# Beilage.net
KiCad netlist of a schematic drawn in EAGLE
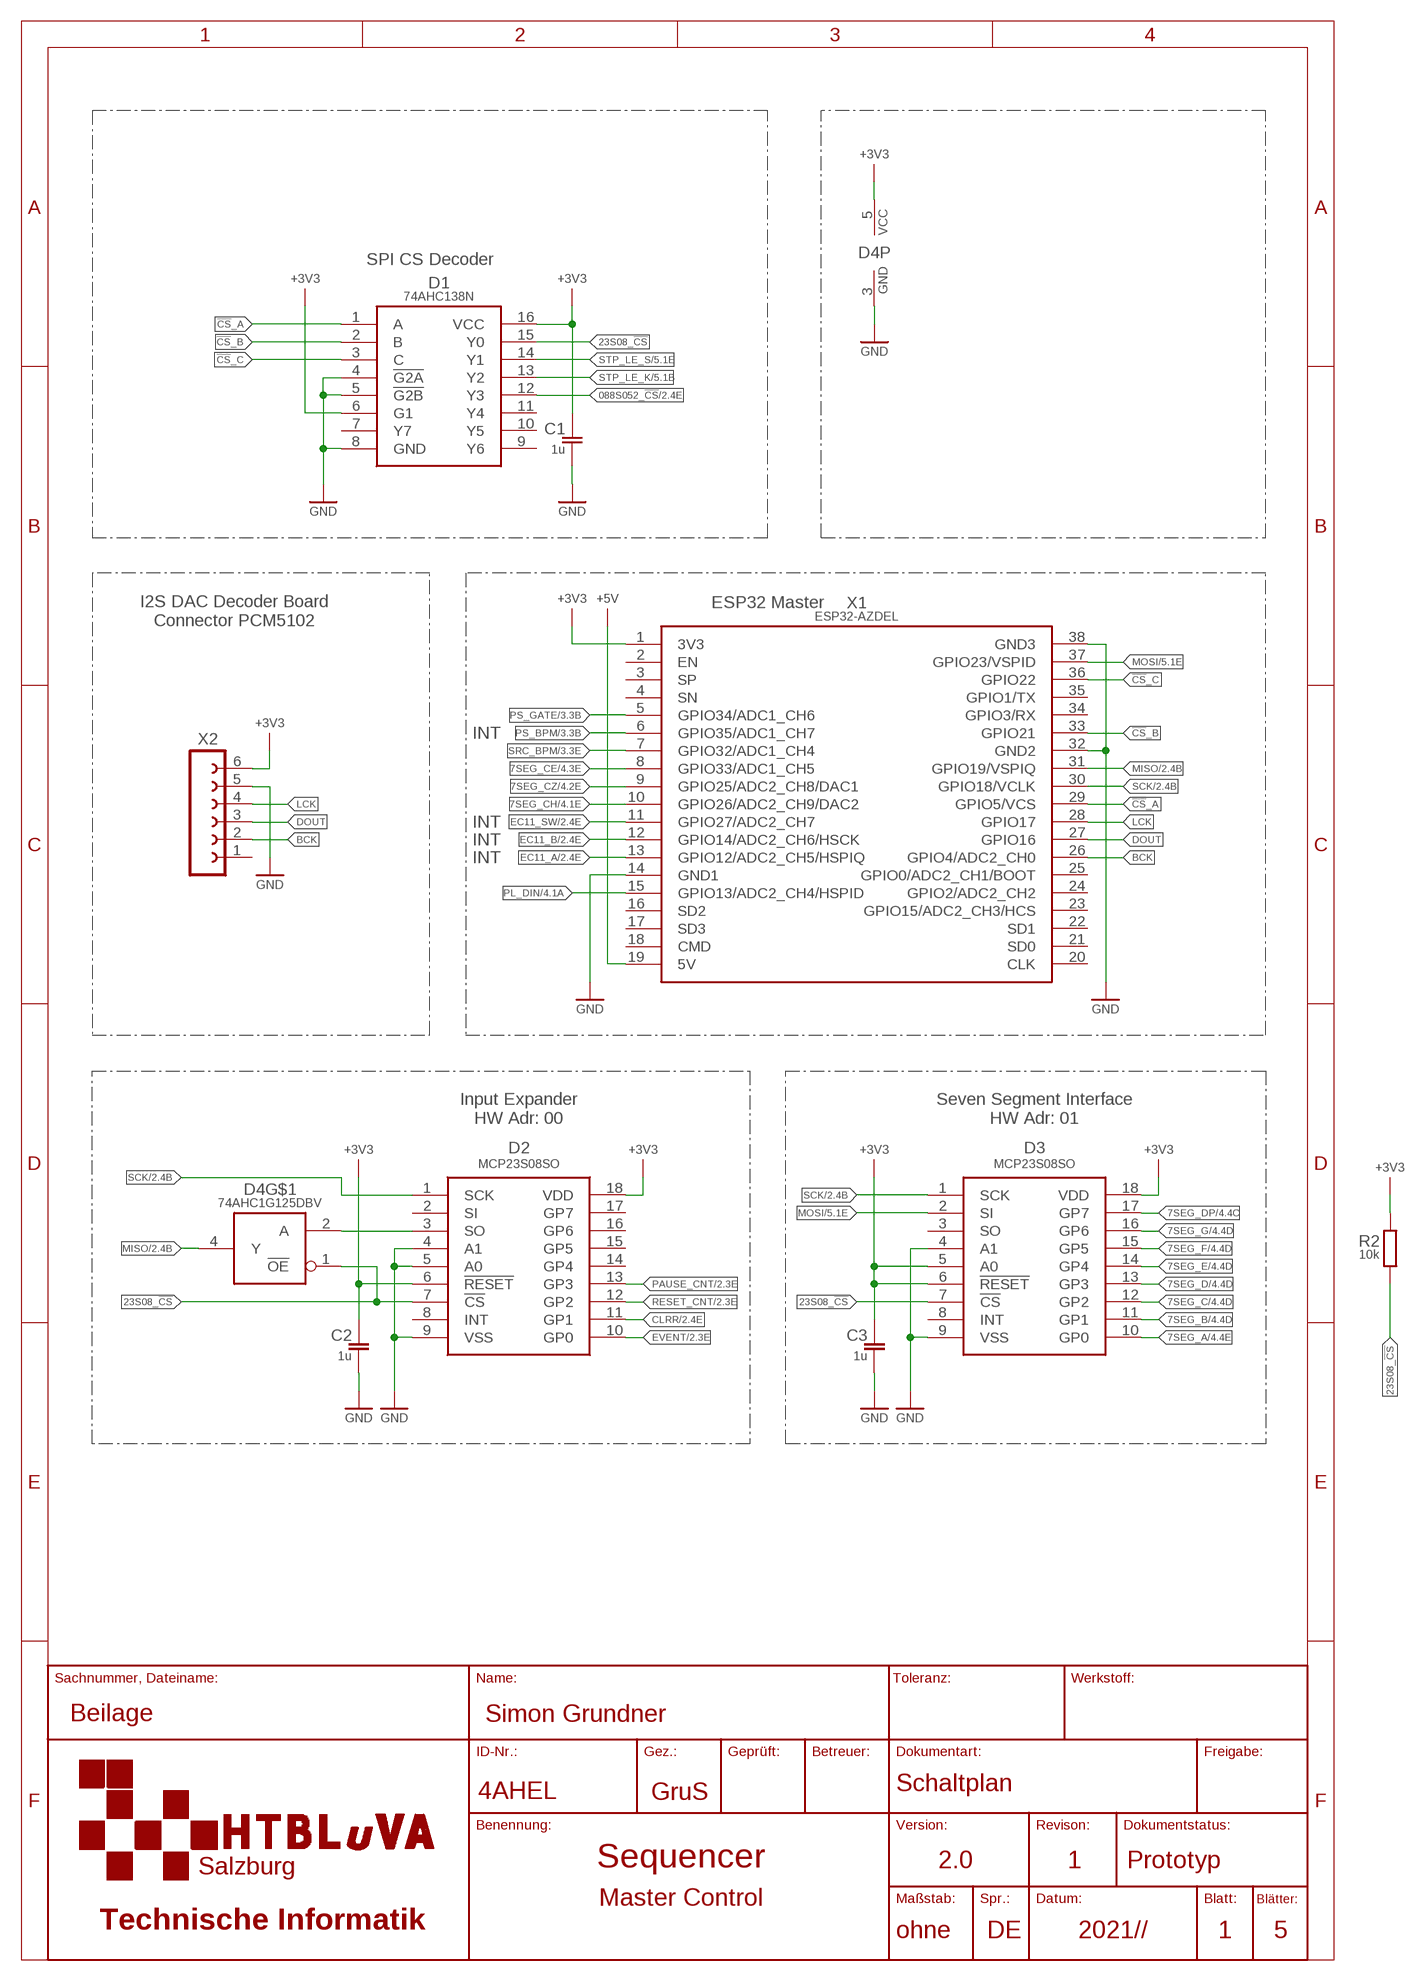
[diagram p0: schematic, sheet 1]
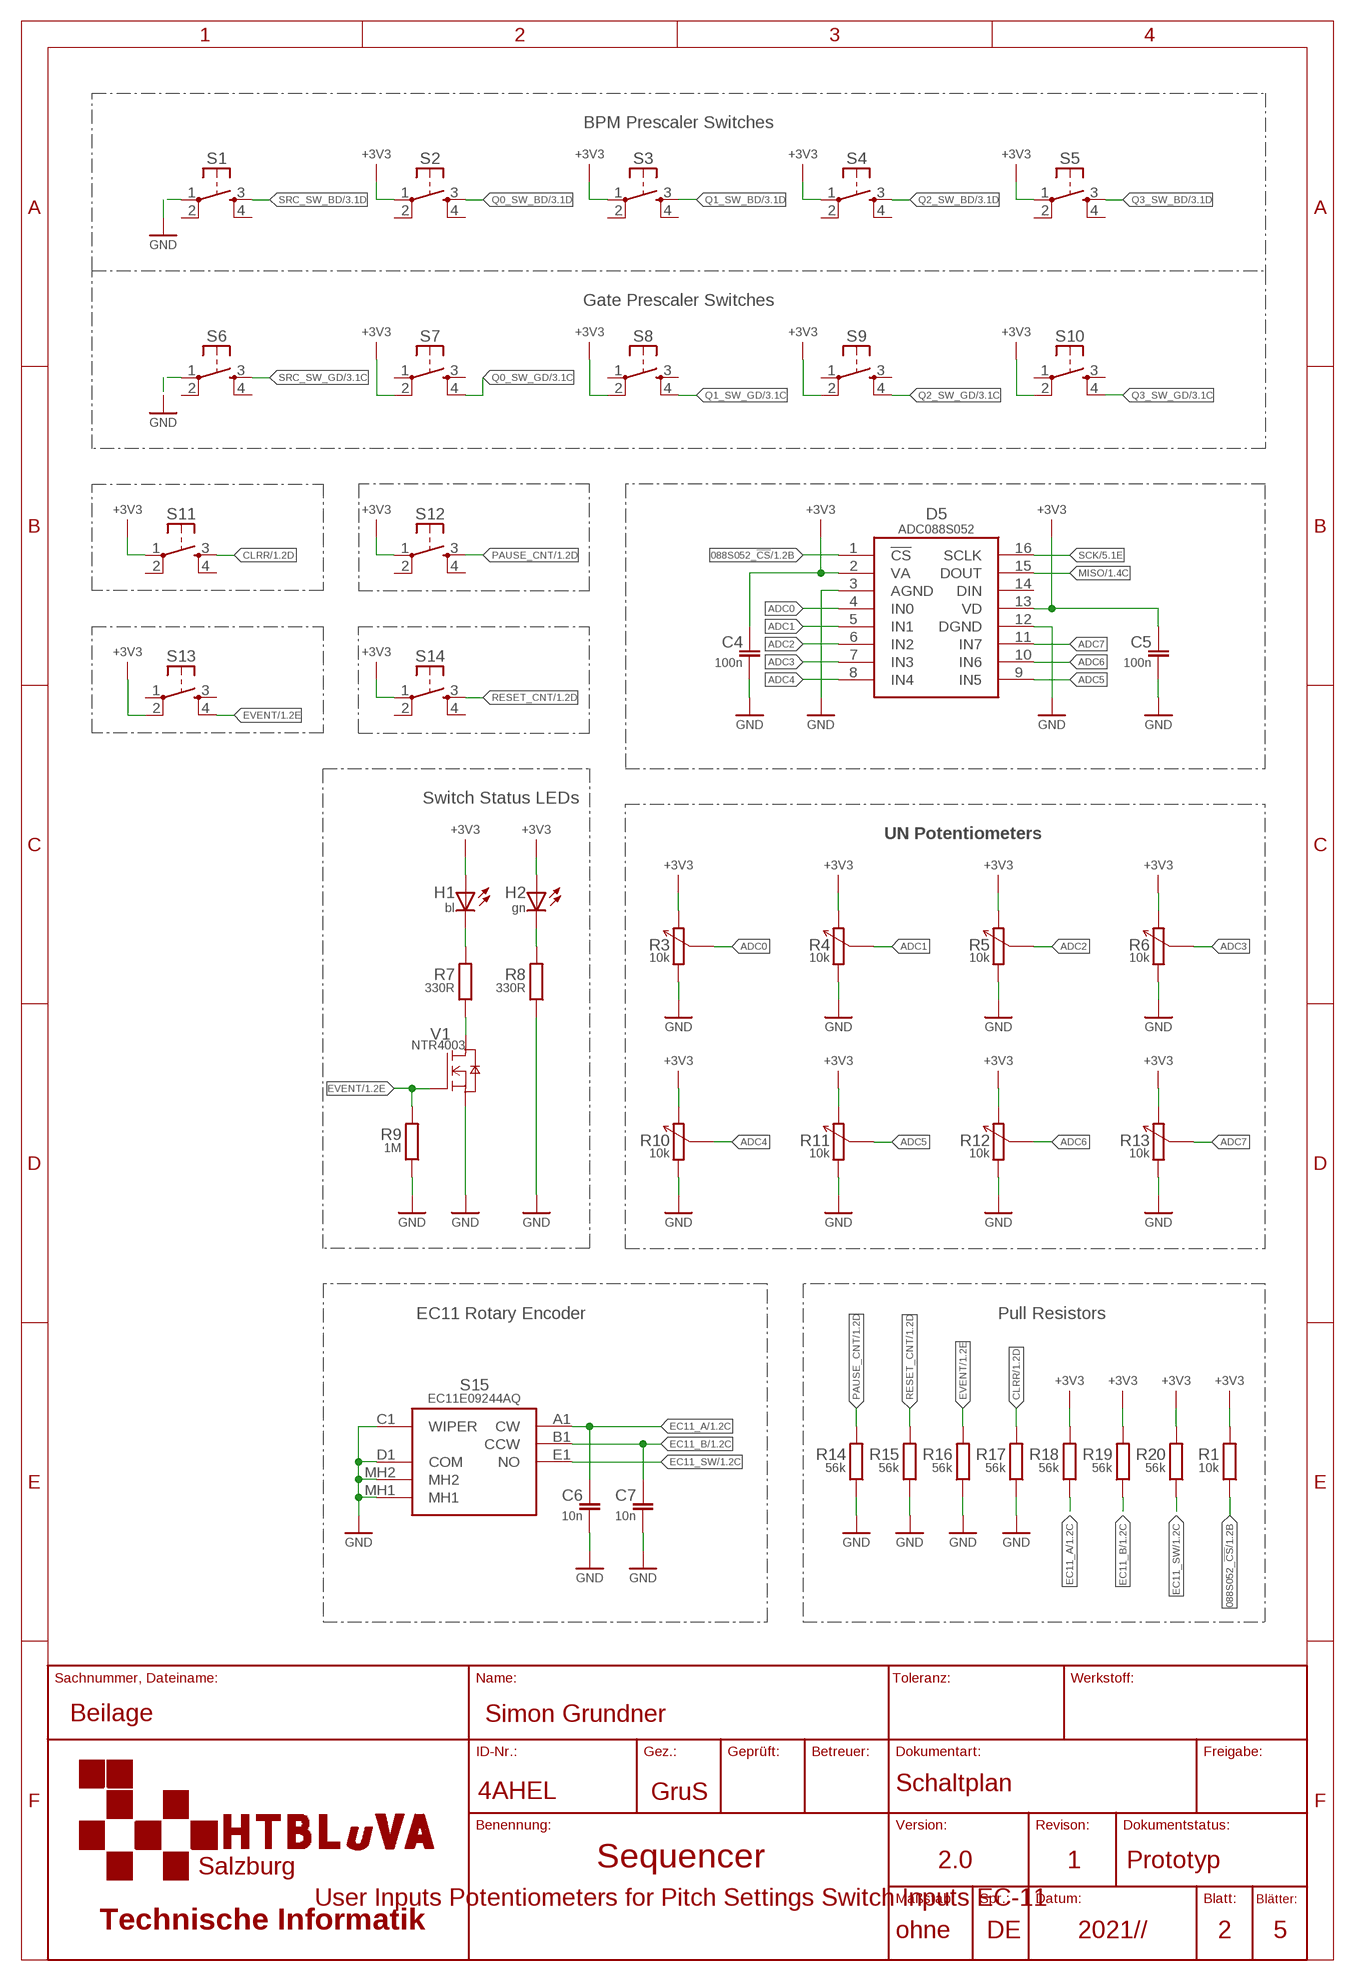
[diagram p1: schematic, sheet 2]
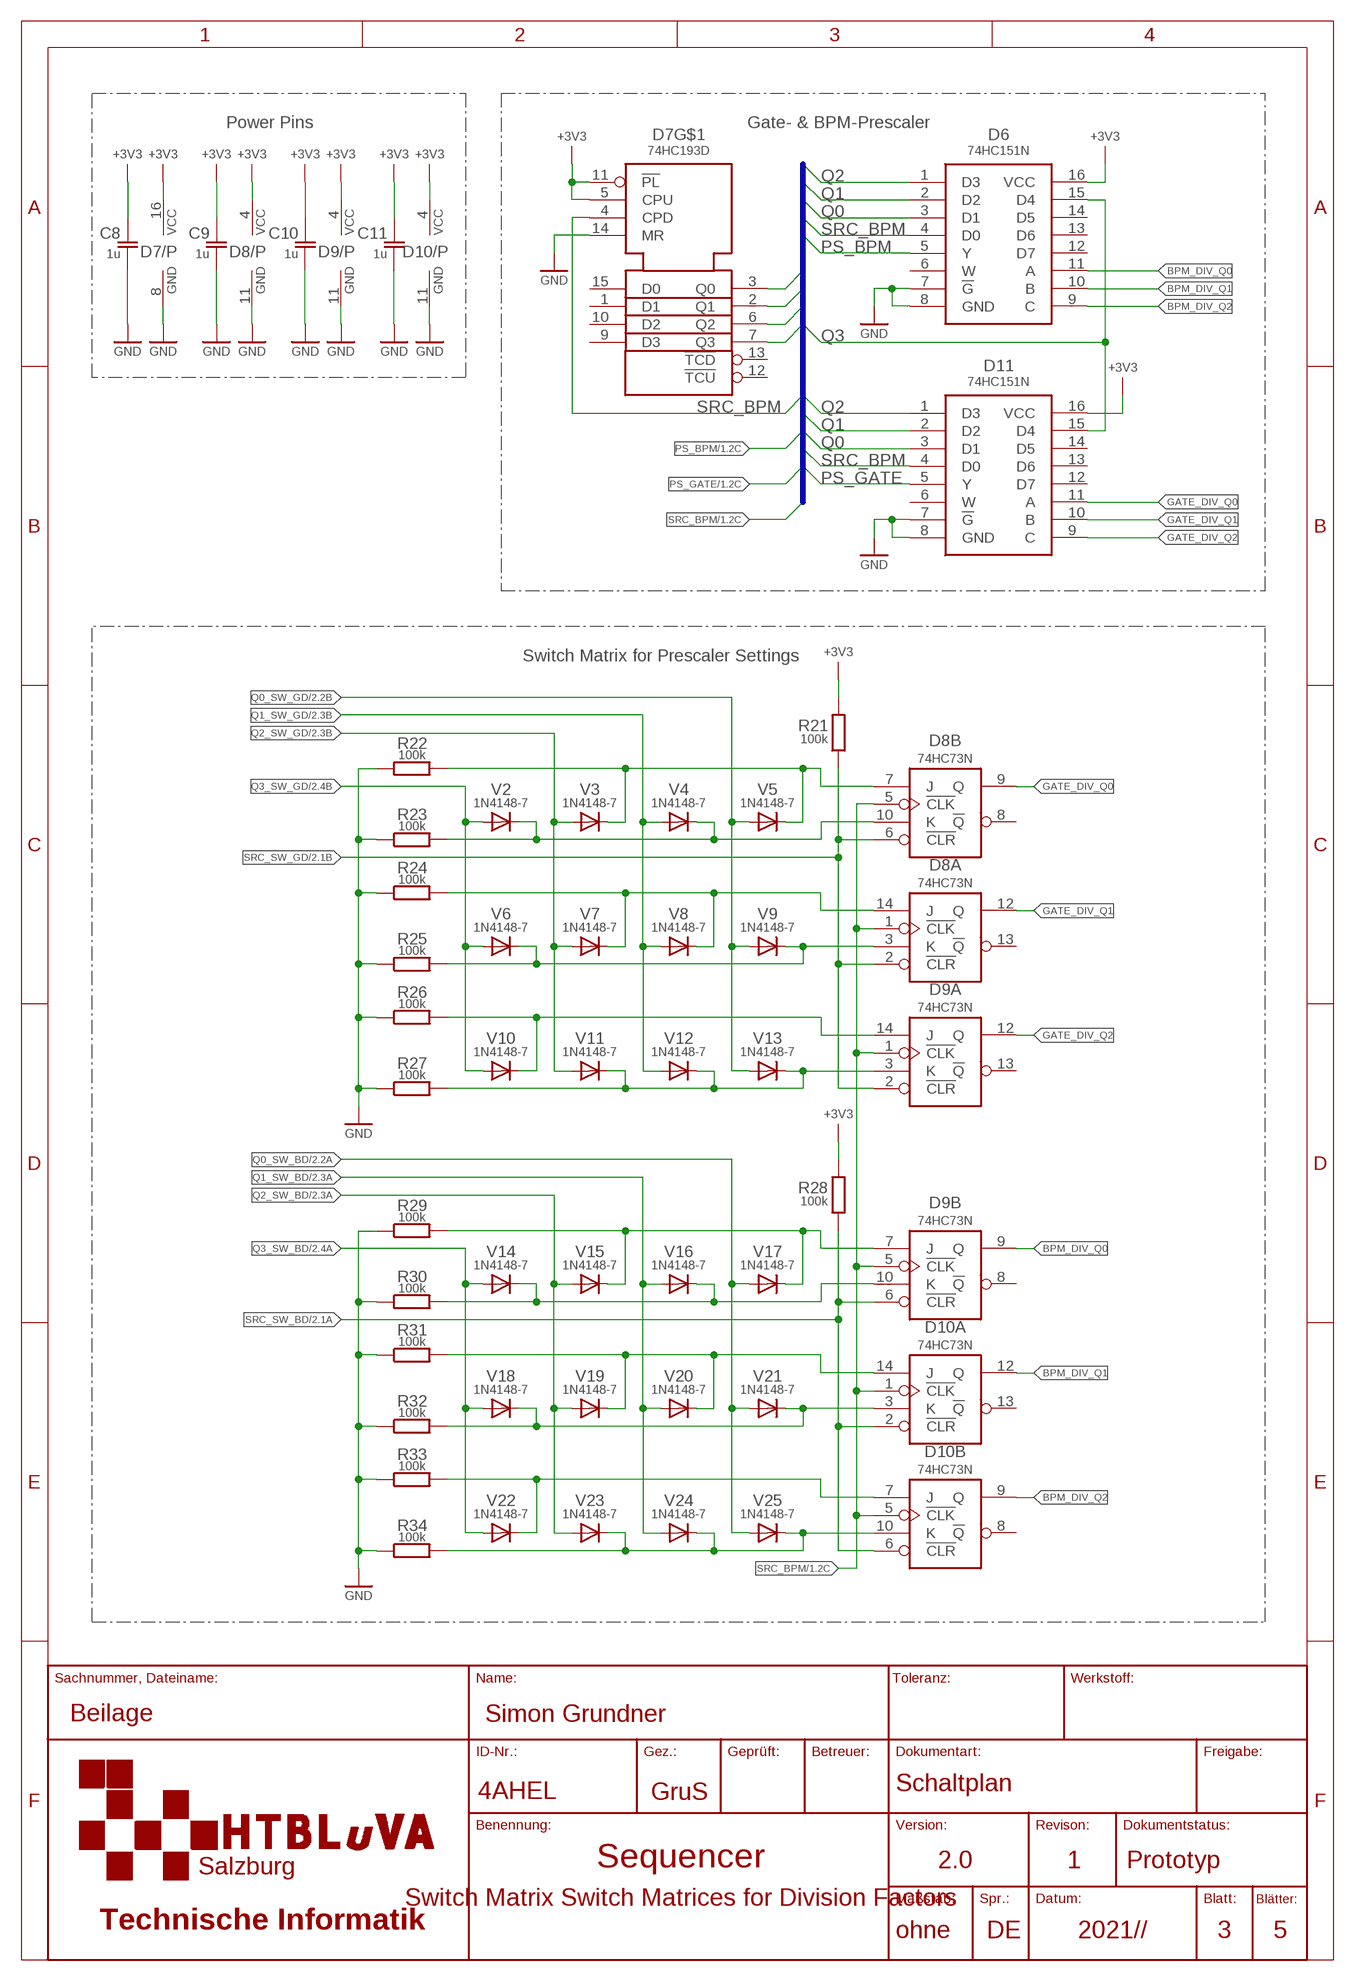
[diagram p2: schematic, sheet 3]
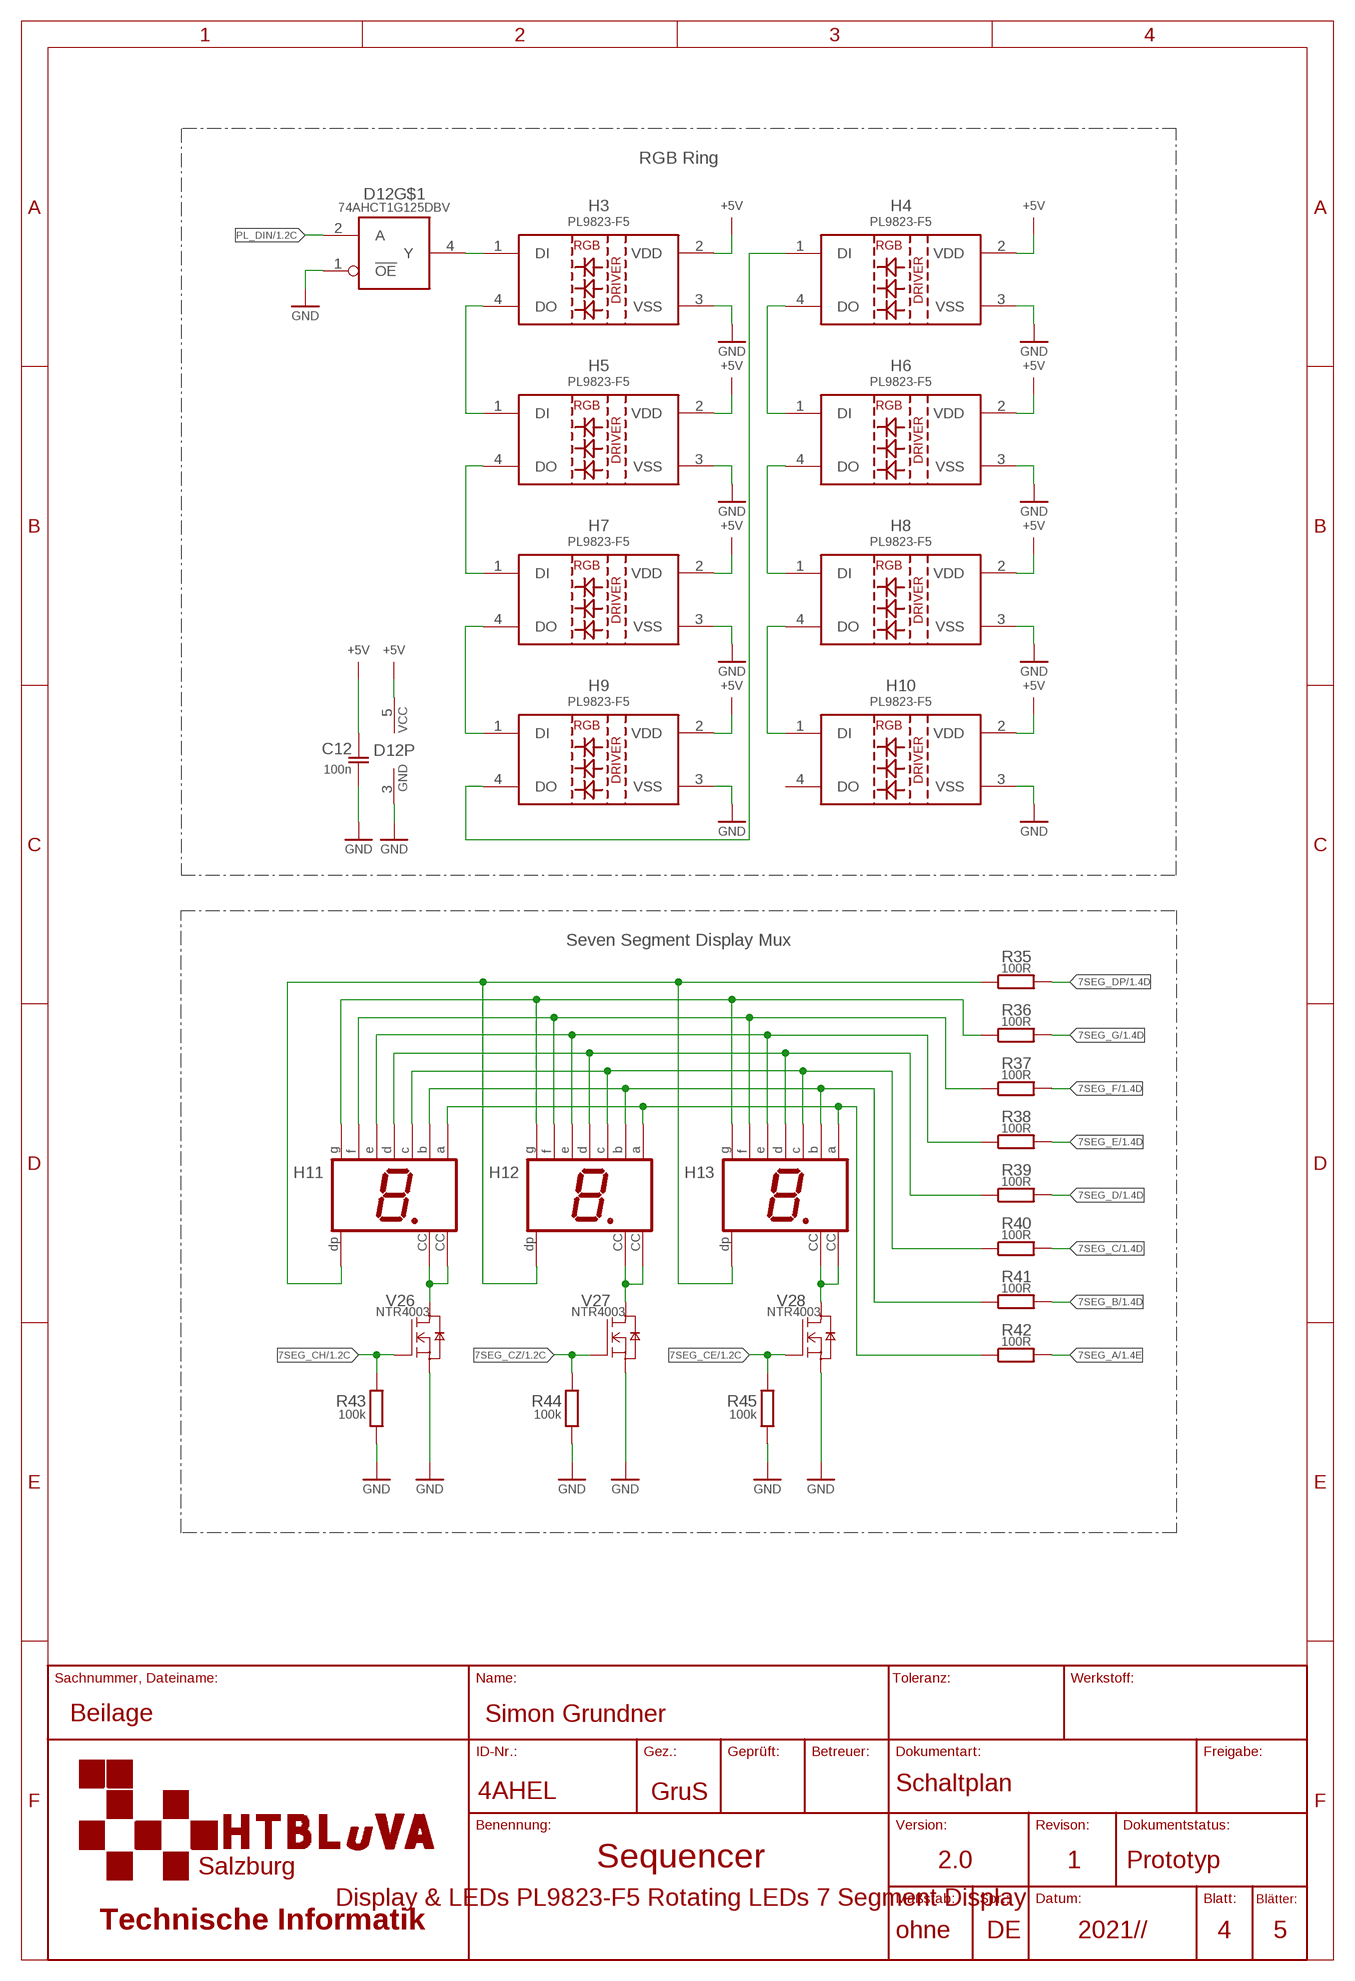
[diagram p3: schematic, sheet 4]
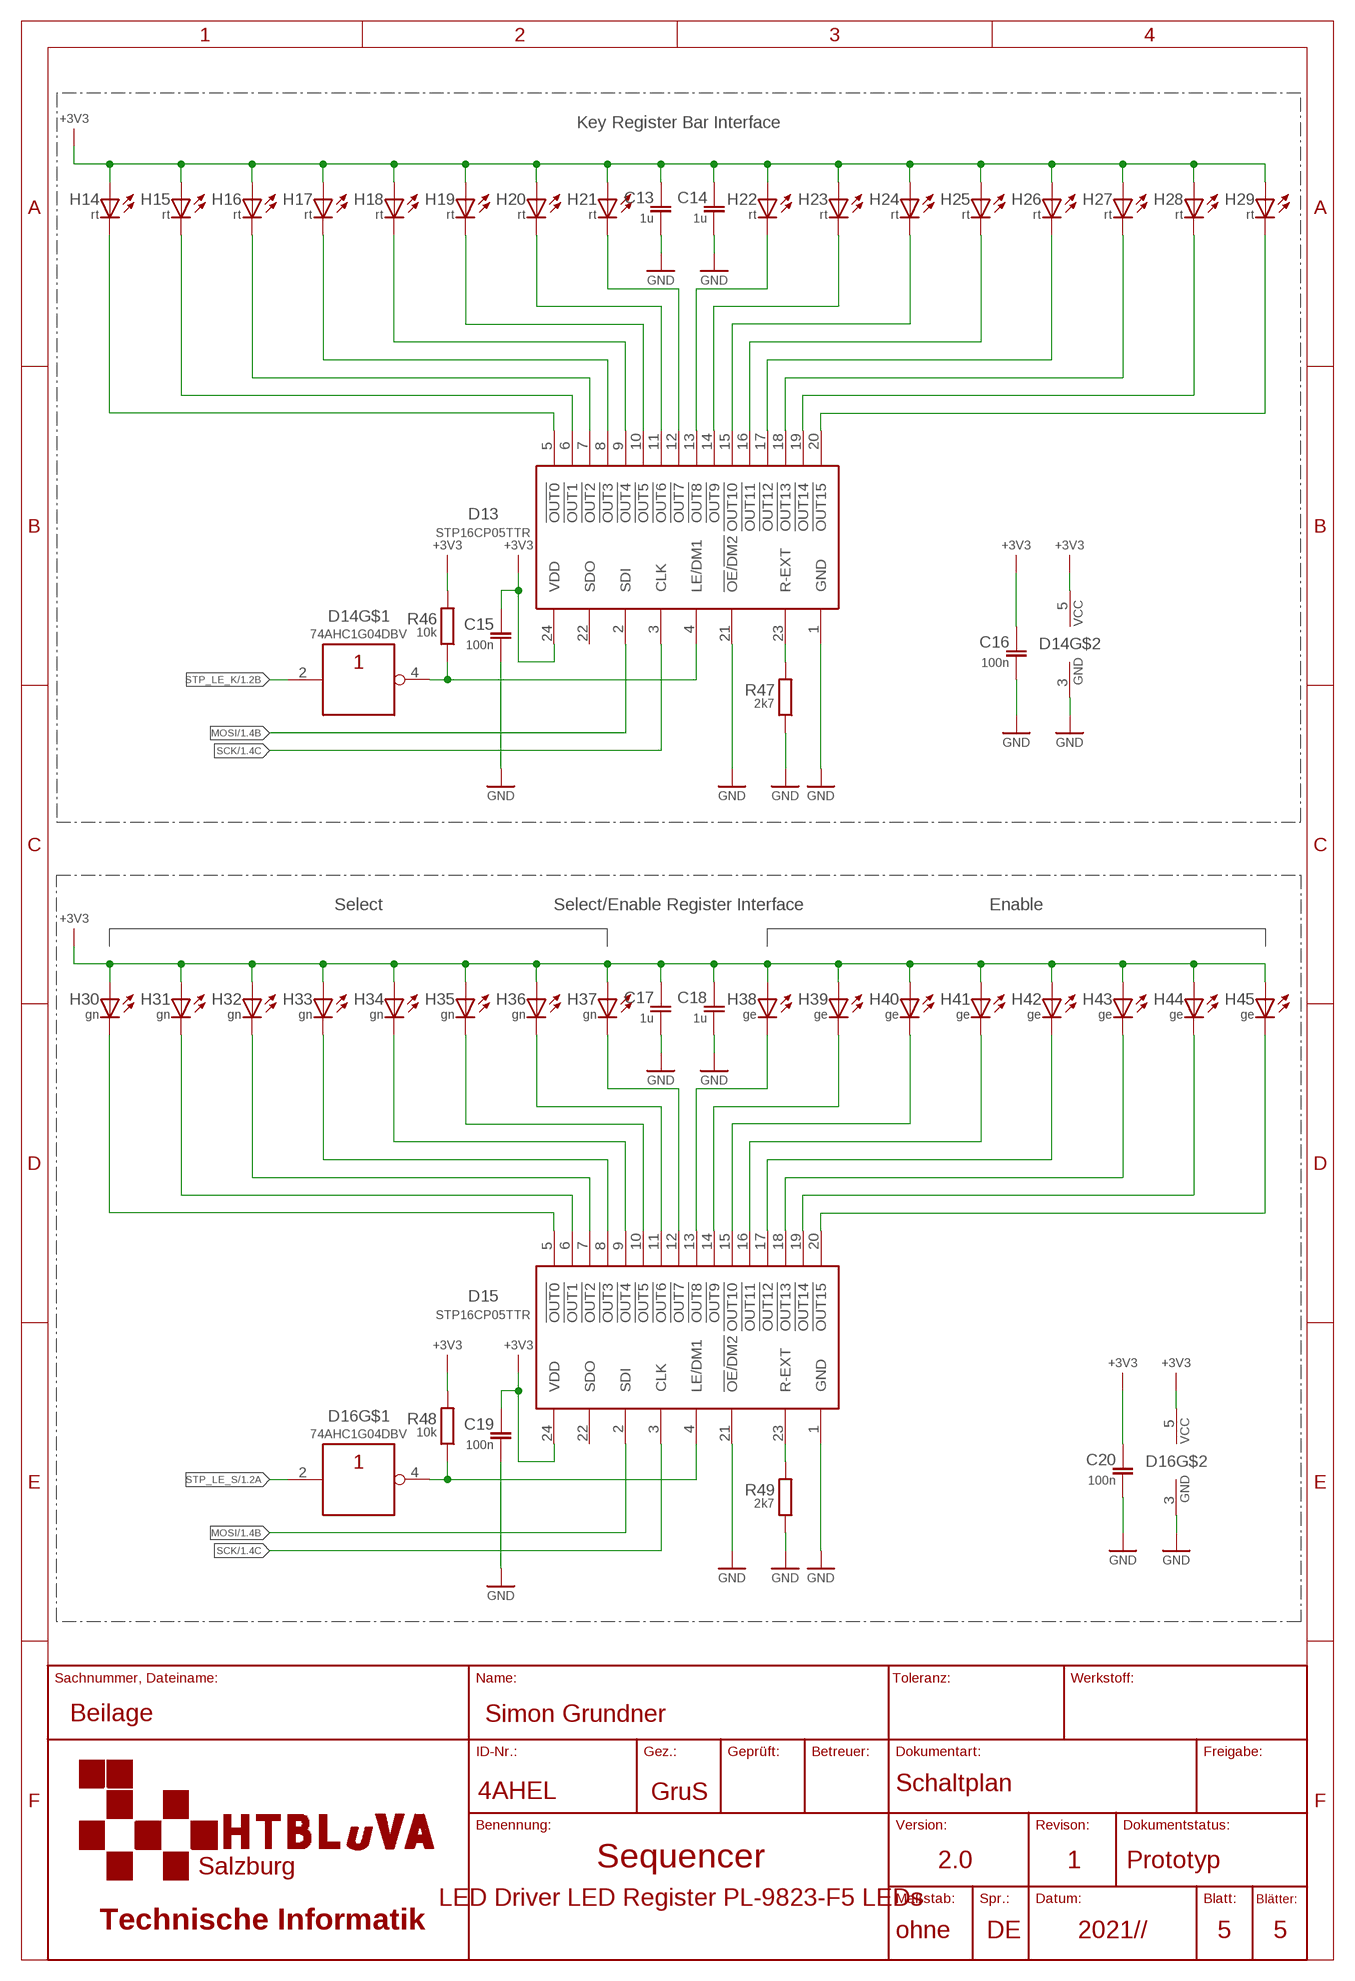
[diagram p4: schematic, sheet 5]

(export (version "E")
  (design (tool "Eeschema 10.0.6"))
  (components
    (comp (ref "C8")
      (value "1u")
      (footprint "eagle-import:C0805")
      (libsource (lib "eagle-import") (part "C-EUC0805"))
    )
    (comp (ref "C9")
      (value "1u")
      (footprint "eagle-import:C0805")
      (libsource (lib "eagle-import") (part "C-EUC0805"))
    )
    (comp (ref "C10")
      (value "1u")
      (footprint "eagle-import:C0805")
      (libsource (lib "eagle-import") (part "C-EUC0805"))
    )
    (comp (ref "C11")
      (value "1u")
      (footprint "eagle-import:C0805")
      (libsource (lib "eagle-import") (part "C-EUC0805"))
    )
    (comp (ref "D6")
      (value "74HC151N")
      (footprint "eagle-import:DIP16")
      (libsource (lib "eagle-import") (part "74151NHC"))
    )
    (comp (ref "D7")
      (value "74HC193D")
      (footprint "eagle-import:SO16")
      (fields (field (name "CATEGORY") "13"))
      (libsource (lib "eagle-import") (part "74193DHC"))
    )
    (comp (ref "D8")
      (value "74HC73N")
      (footprint "eagle-import:DIP14")
      (fields (field (name "CATEGORY") "13"))
      (libsource (lib "eagle-import") (part "7473NHC"))
    )
    (comp (ref "D9")
      (value "74HC73N")
      (footprint "eagle-import:DIP14")
      (fields (field (name "CATEGORY") "13"))
      (libsource (lib "eagle-import") (part "7473NHC"))
    )
    (comp (ref "D10")
      (value "74HC73N")
      (footprint "eagle-import:DIP14")
      (fields (field (name "CATEGORY") "13"))
      (libsource (lib "eagle-import") (part "7473NHC"))
    )
    (comp (ref "D11")
      (value "74HC151N")
      (footprint "eagle-import:DIP16")
      (libsource (lib "eagle-import") (part "74151NHC"))
    )
    (comp (ref "R21")
      (value "100k")
      (footprint "eagle-import:R0805")
      (libsource (lib "eagle-import") (part "R-EUSR0805"))
    )
    (comp (ref "R22")
      (value "100k")
      (footprint "eagle-import:R0805")
      (libsource (lib "eagle-import") (part "R-EU_R0805"))
    )
    (comp (ref "R23")
      (value "100k")
      (footprint "eagle-import:R0805")
      (libsource (lib "eagle-import") (part "R-EU_R0805"))
    )
    (comp (ref "R24")
      (value "100k")
      (footprint "eagle-import:R0805")
      (libsource (lib "eagle-import") (part "R-EU_R0805"))
    )
    (comp (ref "R25")
      (value "100k")
      (footprint "eagle-import:R0805")
      (libsource (lib "eagle-import") (part "R-EU_R0805"))
    )
    (comp (ref "R26")
      (value "100k")
      (footprint "eagle-import:R0805")
      (libsource (lib "eagle-import") (part "R-EU_R0805"))
    )
    (comp (ref "R27")
      (value "100k")
      (footprint "eagle-import:R0805")
      (libsource (lib "eagle-import") (part "R-EU_R0805"))
    )
    (comp (ref "R28")
      (value "100k")
      (footprint "eagle-import:R0805")
      (libsource (lib "eagle-import") (part "R-EUSR0805"))
    )
    (comp (ref "R29")
      (value "100k")
      (footprint "eagle-import:R0805")
      (libsource (lib "eagle-import") (part "R-EU_R0805"))
    )
    (comp (ref "R30")
      (value "100k")
      (footprint "eagle-import:R0805")
      (libsource (lib "eagle-import") (part "R-EU_R0805"))
    )
    (comp (ref "R31")
      (value "100k")
      (footprint "eagle-import:R0805")
      (libsource (lib "eagle-import") (part "R-EU_R0805"))
    )
    (comp (ref "R32")
      (value "100k")
      (footprint "eagle-import:R0805")
      (libsource (lib "eagle-import") (part "R-EU_R0805"))
    )
    (comp (ref "R33")
      (value "100k")
      (footprint "eagle-import:R0805")
      (libsource (lib "eagle-import") (part "R-EU_R0805"))
    )
    (comp (ref "R34")
      (value "100k")
      (footprint "eagle-import:R0805")
      (libsource (lib "eagle-import") (part "R-EU_R0805"))
    )
    (comp (ref "V2")
      (value "1N4148-7")
      (footprint "eagle-import:DO35-7")
      (libsource (lib "eagle-import") (part "1N4148-7"))
    )
    (comp (ref "V3")
      (value "1N4148-7")
      (footprint "eagle-import:DO35-7")
      (libsource (lib "eagle-import") (part "1N4148-7"))
    )
    (comp (ref "V4")
      (value "1N4148-7")
      (footprint "eagle-import:DO35-7")
      (libsource (lib "eagle-import") (part "1N4148-7"))
    )
    (comp (ref "V5")
      (value "1N4148-7")
      (footprint "eagle-import:DO35-7")
      (libsource (lib "eagle-import") (part "1N4148-7"))
    )
    (comp (ref "V6")
      (value "1N4148-7")
      (footprint "eagle-import:DO35-7")
      (libsource (lib "eagle-import") (part "1N4148-7"))
    )
    (comp (ref "V7")
      (value "1N4148-7")
      (footprint "eagle-import:DO35-7")
      (libsource (lib "eagle-import") (part "1N4148-7"))
    )
    (comp (ref "V8")
      (value "1N4148-7")
      (footprint "eagle-import:DO35-7")
      (libsource (lib "eagle-import") (part "1N4148-7"))
    )
    (comp (ref "V9")
      (value "1N4148-7")
      (footprint "eagle-import:DO35-7")
      (libsource (lib "eagle-import") (part "1N4148-7"))
    )
    (comp (ref "V10")
      (value "1N4148-7")
      (footprint "eagle-import:DO35-7")
      (libsource (lib "eagle-import") (part "1N4148-7"))
    )
    (comp (ref "V11")
      (value "1N4148-7")
      (footprint "eagle-import:DO35-7")
      (libsource (lib "eagle-import") (part "1N4148-7"))
    )
    (comp (ref "V12")
      (value "1N4148-7")
      (footprint "eagle-import:DO35-7")
      (libsource (lib "eagle-import") (part "1N4148-7"))
    )
    (comp (ref "V13")
      (value "1N4148-7")
      (footprint "eagle-import:DO35-7")
      (libsource (lib "eagle-import") (part "1N4148-7"))
    )
    (comp (ref "V14")
      (value "1N4148-7")
      (footprint "eagle-import:DO35-7")
      (libsource (lib "eagle-import") (part "1N4148-7"))
    )
    (comp (ref "V15")
      (value "1N4148-7")
      (footprint "eagle-import:DO35-7")
      (libsource (lib "eagle-import") (part "1N4148-7"))
    )
    (comp (ref "V16")
      (value "1N4148-7")
      (footprint "eagle-import:DO35-7")
      (libsource (lib "eagle-import") (part "1N4148-7"))
    )
    (comp (ref "V17")
      (value "1N4148-7")
      (footprint "eagle-import:DO35-7")
      (libsource (lib "eagle-import") (part "1N4148-7"))
    )
    (comp (ref "V18")
      (value "1N4148-7")
      (footprint "eagle-import:DO35-7")
      (libsource (lib "eagle-import") (part "1N4148-7"))
    )
    (comp (ref "V19")
      (value "1N4148-7")
      (footprint "eagle-import:DO35-7")
      (libsource (lib "eagle-import") (part "1N4148-7"))
    )
    (comp (ref "V20")
      (value "1N4148-7")
      (footprint "eagle-import:DO35-7")
      (libsource (lib "eagle-import") (part "1N4148-7"))
    )
    (comp (ref "V21")
      (value "1N4148-7")
      (footprint "eagle-import:DO35-7")
      (libsource (lib "eagle-import") (part "1N4148-7"))
    )
    (comp (ref "V22")
      (value "1N4148-7")
      (footprint "eagle-import:DO35-7")
      (libsource (lib "eagle-import") (part "1N4148-7"))
    )
    (comp (ref "V23")
      (value "1N4148-7")
      (footprint "eagle-import:DO35-7")
      (libsource (lib "eagle-import") (part "1N4148-7"))
    )
    (comp (ref "V24")
      (value "1N4148-7")
      (footprint "eagle-import:DO35-7")
      (libsource (lib "eagle-import") (part "1N4148-7"))
    )
    (comp (ref "V25")
      (value "1N4148-7")
      (footprint "eagle-import:DO35-7")
      (libsource (lib "eagle-import") (part "1N4148-7"))
    )
    (comp (ref "C13")
      (value "1u")
      (footprint "eagle-import:C0805")
      (libsource (lib "eagle-import") (part "C-EUC0805"))
    )
    (comp (ref "C14")
      (value "1u")
      (footprint "eagle-import:C0805")
      (libsource (lib "eagle-import") (part "C-EUC0805"))
    )
    (comp (ref "C15")
      (value "100n")
      (footprint "eagle-import:C0805")
      (libsource (lib "eagle-import") (part "C-EUC0805"))
    )
    (comp (ref "C16")
      (value "100n")
      (footprint "eagle-import:C0805")
      (libsource (lib "eagle-import") (part "C-EUC0805"))
    )
    (comp (ref "C17")
      (value "1u")
      (footprint "eagle-import:C0805")
      (libsource (lib "eagle-import") (part "C-EUC0805"))
    )
    (comp (ref "C18")
      (value "1u")
      (footprint "eagle-import:C0805")
      (libsource (lib "eagle-import") (part "C-EUC0805"))
    )
    (comp (ref "C19")
      (value "100n")
      (footprint "eagle-import:C0805")
      (libsource (lib "eagle-import") (part "C-EUC0805"))
    )
    (comp (ref "C20")
      (value "100n")
      (footprint "eagle-import:C0805")
      (libsource (lib "eagle-import") (part "C-EUC0805"))
    )
    (comp (ref "D13")
      (value "STP16CP05TTR")
      (footprint "eagle-import:TSSOP24")
      (libsource (lib "eagle-import") (part "STP16CP05TTR"))
    )
    (comp (ref "D14")
      (value "74AHC1G04DBV")
      (footprint "eagle-import:SOT23-5")
      (libsource (lib "eagle-import") (part "741G04DBVAHC"))
    )
    (comp (ref "D15")
      (value "STP16CP05TTR")
      (footprint "eagle-import:TSSOP24")
      (libsource (lib "eagle-import") (part "STP16CP05TTR"))
    )
    (comp (ref "D16")
      (value "74AHC1G04DBV")
      (footprint "eagle-import:SOT23-5")
      (libsource (lib "eagle-import") (part "741G04DBVAHC"))
    )
    (comp (ref "H14")
      (value "rt")
      (footprint "eagle-import:CHIPLED_1206")
      (libsource (lib "eagle-import") (part "LEDCHIPLED_1206"))
    )
    (comp (ref "H15")
      (value "rt")
      (footprint "eagle-import:CHIPLED_1206")
      (libsource (lib "eagle-import") (part "LEDCHIPLED_1206"))
    )
    (comp (ref "H16")
      (value "rt")
      (footprint "eagle-import:CHIPLED_1206")
      (libsource (lib "eagle-import") (part "LEDCHIPLED_1206"))
    )
    (comp (ref "H17")
      (value "rt")
      (footprint "eagle-import:CHIPLED_1206")
      (libsource (lib "eagle-import") (part "LEDCHIPLED_1206"))
    )
    (comp (ref "H18")
      (value "rt")
      (footprint "eagle-import:CHIPLED_1206")
      (libsource (lib "eagle-import") (part "LEDCHIPLED_1206"))
    )
    (comp (ref "H19")
      (value "rt")
      (footprint "eagle-import:CHIPLED_1206")
      (libsource (lib "eagle-import") (part "LEDCHIPLED_1206"))
    )
    (comp (ref "H20")
      (value "rt")
      (footprint "eagle-import:CHIPLED_1206")
      (libsource (lib "eagle-import") (part "LEDCHIPLED_1206"))
    )
    (comp (ref "H21")
      (value "rt")
      (footprint "eagle-import:CHIPLED_1206")
      (libsource (lib "eagle-import") (part "LEDCHIPLED_1206"))
    )
    (comp (ref "H22")
      (value "rt")
      (footprint "eagle-import:CHIPLED_1206")
      (libsource (lib "eagle-import") (part "LEDCHIPLED_1206"))
    )
    (comp (ref "H23")
      (value "rt")
      (footprint "eagle-import:CHIPLED_1206")
      (libsource (lib "eagle-import") (part "LEDCHIPLED_1206"))
    )
    (comp (ref "H24")
      (value "rt")
      (footprint "eagle-import:CHIPLED_1206")
      (libsource (lib "eagle-import") (part "LEDCHIPLED_1206"))
    )
    (comp (ref "H25")
      (value "rt")
      (footprint "eagle-import:CHIPLED_1206")
      (libsource (lib "eagle-import") (part "LEDCHIPLED_1206"))
    )
    (comp (ref "H26")
      (value "rt")
      (footprint "eagle-import:CHIPLED_1206")
      (libsource (lib "eagle-import") (part "LEDCHIPLED_1206"))
    )
    (comp (ref "H27")
      (value "rt")
      (footprint "eagle-import:CHIPLED_1206")
      (libsource (lib "eagle-import") (part "LEDCHIPLED_1206"))
    )
    (comp (ref "H28")
      (value "rt")
      (footprint "eagle-import:CHIPLED_1206")
      (libsource (lib "eagle-import") (part "LEDCHIPLED_1206"))
    )
    (comp (ref "H29")
      (value "rt")
      (footprint "eagle-import:CHIPLED_1206")
      (libsource (lib "eagle-import") (part "LEDCHIPLED_1206"))
    )
    (comp (ref "H30")
      (value "gn")
      (footprint "eagle-import:LED5MM")
      (libsource (lib "eagle-import") (part "LED5MM"))
    )
    (comp (ref "H31")
      (value "gn")
      (footprint "eagle-import:LED5MM")
      (libsource (lib "eagle-import") (part "LED5MM"))
    )
    (comp (ref "H32")
      (value "gn")
      (footprint "eagle-import:LED5MM")
      (libsource (lib "eagle-import") (part "LED5MM"))
    )
    (comp (ref "H33")
      (value "gn")
      (footprint "eagle-import:LED5MM")
      (libsource (lib "eagle-import") (part "LED5MM"))
    )
    (comp (ref "H34")
      (value "gn")
      (footprint "eagle-import:LED5MM")
      (libsource (lib "eagle-import") (part "LED5MM"))
    )
    (comp (ref "H35")
      (value "gn")
      (footprint "eagle-import:LED5MM")
      (libsource (lib "eagle-import") (part "LED5MM"))
    )
    (comp (ref "H36")
      (value "gn")
      (footprint "eagle-import:LED5MM")
      (libsource (lib "eagle-import") (part "LED5MM"))
    )
    (comp (ref "H37")
      (value "gn")
      (footprint "eagle-import:LED5MM")
      (libsource (lib "eagle-import") (part "LED5MM"))
    )
    (comp (ref "H38")
      (value "ge")
      (footprint "eagle-import:LED5MM")
      (libsource (lib "eagle-import") (part "LED5MM"))
    )
    (comp (ref "H39")
      (value "ge")
      (footprint "eagle-import:LED5MM")
      (libsource (lib "eagle-import") (part "LED5MM"))
    )
    (comp (ref "H40")
      (value "ge")
      (footprint "eagle-import:LED5MM")
      (libsource (lib "eagle-import") (part "LED5MM"))
    )
    (comp (ref "H41")
      (value "ge")
      (footprint "eagle-import:LED5MM")
      (libsource (lib "eagle-import") (part "LED5MM"))
    )
    (comp (ref "H42")
      (value "ge")
      (footprint "eagle-import:LED5MM")
      (libsource (lib "eagle-import") (part "LED5MM"))
    )
    (comp (ref "H43")
      (value "ge")
      (footprint "eagle-import:LED5MM")
      (libsource (lib "eagle-import") (part "LED5MM"))
    )
    (comp (ref "H44")
      (value "ge")
      (footprint "eagle-import:LED5MM")
      (libsource (lib "eagle-import") (part "LED5MM"))
    )
    (comp (ref "H45")
      (value "ge")
      (footprint "eagle-import:LED5MM")
      (libsource (lib "eagle-import") (part "LED5MM"))
    )
    (comp (ref "R46")
      (value "10k")
      (footprint "eagle-import:R0805")
      (libsource (lib "eagle-import") (part "R-EUSR0805"))
    )
    (comp (ref "R47")
      (value "2k7")
      (footprint "eagle-import:R0805")
      (libsource (lib "eagle-import") (part "R-EUSR0805"))
    )
    (comp (ref "R48")
      (value "10k")
      (footprint "eagle-import:R0805")
      (libsource (lib "eagle-import") (part "R-EUSR0805"))
    )
    (comp (ref "R49")
      (value "2k7")
      (footprint "eagle-import:R0805")
      (libsource (lib "eagle-import") (part "R-EUSR0805"))
    )
    (comp (ref "C1")
      (value "1u")
      (footprint "eagle-import:C0805")
      (libsource (lib "eagle-import") (part "C-EUC0805"))
    )
    (comp (ref "C2")
      (value "1u")
      (footprint "eagle-import:C0805")
      (libsource (lib "eagle-import") (part "C-EUC0805"))
    )
    (comp (ref "C3")
      (value "1u")
      (footprint "eagle-import:C0805")
      (libsource (lib "eagle-import") (part "C-EUC0805"))
    )
    (comp (ref "D1")
      (value "74AHC138N")
      (footprint "eagle-import:DIP16")
      (libsource (lib "eagle-import") (part "74138NAHC"))
    )
    (comp (ref "D2")
      (value "MCP23S08SO")
      (footprint "eagle-import:SO18W")
      (fields
        (field (name "ARROW_PART_NUMBER") "MCP23S08-E/SO")
        (field (name "MOUSER_PART_NUMBER") "579-MCP23S08-E/SO")
      )
      (libsource (lib "eagle-import") (part "MCP23S08SO"))
    )
    (comp (ref "D3")
      (value "MCP23S08SO")
      (footprint "eagle-import:SO18W")
      (fields
        (field (name "ARROW_PART_NUMBER") "MCP23S08-E/SO")
        (field (name "MOUSER_PART_NUMBER") "579-MCP23S08-E/SO")
      )
      (libsource (lib "eagle-import") (part "MCP23S08SO"))
    )
    (comp (ref "D4")
      (value "74AHC1G125DBV")
      (footprint "eagle-import:SOT23-5")
      (libsource (lib "eagle-import") (part "741G125DBVAHC"))
    )
    (comp (ref "R2")
      (value "10k")
      (footprint "eagle-import:R0805")
      (libsource (lib "eagle-import") (part "R-EUSR0805"))
    )
    (comp (ref "X1")
      (value "ESP32-AZDEL")
      (footprint "eagle-import:ESP32-AZDEL")
      (libsource (lib "eagle-import") (part "ESP32-AZDEL"))
    )
    (comp (ref "X2")
      (value "FE06-1")
      (footprint "eagle-import:FE06")
      (libsource (lib "eagle-import") (part "FE06-1"))
    )
    (comp (ref "C12")
      (value "100n")
      (footprint "eagle-import:C0805")
      (libsource (lib "eagle-import") (part "C-EUC0805"))
    )
    (comp (ref "D12")
      (value "74AHCT1G125DBV")
      (footprint "eagle-import:SOT23-5")
      (fields (field (name "CATEGORY") "13"))
      (libsource (lib "eagle-import") (part "741G125DBVAHCT"))
    )
    (comp (ref "H3")
      (value "PL9823-F5")
      (footprint "eagle-import:LED-PL9823-F5")
      (libsource (lib "eagle-import") (part "PL9823-F5"))
    )
    (comp (ref "H4")
      (value "PL9823-F5")
      (footprint "eagle-import:LED-PL9823-F5")
      (libsource (lib "eagle-import") (part "PL9823-F5"))
    )
    (comp (ref "H5")
      (value "PL9823-F5")
      (footprint "eagle-import:LED-PL9823-F5")
      (libsource (lib "eagle-import") (part "PL9823-F5"))
    )
    (comp (ref "H6")
      (value "PL9823-F5")
      (footprint "eagle-import:LED-PL9823-F5")
      (libsource (lib "eagle-import") (part "PL9823-F5"))
    )
    (comp (ref "H7")
      (value "PL9823-F5")
      (footprint "eagle-import:LED-PL9823-F5")
      (libsource (lib "eagle-import") (part "PL9823-F5"))
    )
    (comp (ref "H8")
      (value "PL9823-F5")
      (footprint "eagle-import:LED-PL9823-F5")
      (libsource (lib "eagle-import") (part "PL9823-F5"))
    )
    (comp (ref "H9")
      (value "PL9823-F5")
      (footprint "eagle-import:LED-PL9823-F5")
      (libsource (lib "eagle-import") (part "PL9823-F5"))
    )
    (comp (ref "H10")
      (value "PL9823-F5")
      (footprint "eagle-import:LED-PL9823-F5")
      (libsource (lib "eagle-import") (part "PL9823-F5"))
    )
    (comp (ref "H11")
      (value "HD-H103")
      (footprint "eagle-import:HDSP-E")
      (libsource (lib "eagle-import") (part "HD-H103"))
    )
    (comp (ref "H12")
      (value "HD-H103")
      (footprint "eagle-import:HDSP-E")
      (libsource (lib "eagle-import") (part "HD-H103"))
    )
    (comp (ref "H13")
      (value "HD-H103")
      (footprint "eagle-import:HDSP-E")
      (libsource (lib "eagle-import") (part "HD-H103"))
    )
    (comp (ref "R35")
      (value "100R")
      (footprint "eagle-import:R0805")
      (libsource (lib "eagle-import") (part "R-EU_R0805"))
    )
    (comp (ref "R36")
      (value "100R")
      (footprint "eagle-import:R0805")
      (libsource (lib "eagle-import") (part "R-EU_R0805"))
    )
    (comp (ref "R37")
      (value "100R")
      (footprint "eagle-import:R0805")
      (libsource (lib "eagle-import") (part "R-EU_R0805"))
    )
    (comp (ref "R38")
      (value "100R")
      (footprint "eagle-import:R0805")
      (libsource (lib "eagle-import") (part "R-EU_R0805"))
    )
    (comp (ref "R39")
      (value "100R")
      (footprint "eagle-import:R0805")
      (libsource (lib "eagle-import") (part "R-EU_R0805"))
    )
    (comp (ref "R40")
      (value "100R")
      (footprint "eagle-import:R0805")
      (libsource (lib "eagle-import") (part "R-EU_R0805"))
    )
    (comp (ref "R41")
      (value "100R")
      (footprint "eagle-import:R0805")
      (libsource (lib "eagle-import") (part "R-EU_R0805"))
    )
    (comp (ref "R42")
      (value "100R")
      (footprint "eagle-import:R0805")
      (libsource (lib "eagle-import") (part "R-EU_R0805"))
    )
    (comp (ref "R43")
      (value "100k")
      (footprint "eagle-import:R0805")
      (libsource (lib "eagle-import") (part "R-EUSR0805"))
    )
    (comp (ref "R44")
      (value "100k")
      (footprint "eagle-import:R0805")
      (libsource (lib "eagle-import") (part "R-EUSR0805"))
    )
    (comp (ref "R45")
      (value "100k")
      (footprint "eagle-import:R0805")
      (libsource (lib "eagle-import") (part "R-EUSR0805"))
    )
    (comp (ref "V26")
      (value "NTR4003")
      (footprint "eagle-import:SOT23")
      (libsource (lib "eagle-import") (part "NTR4003"))
    )
    (comp (ref "V27")
      (value "NTR4003")
      (footprint "eagle-import:SOT23")
      (libsource (lib "eagle-import") (part "NTR4003"))
    )
    (comp (ref "V28")
      (value "NTR4003")
      (footprint "eagle-import:SOT23")
      (libsource (lib "eagle-import") (part "NTR4003"))
    )
    (comp (ref "C4")
      (value "100n")
      (footprint "eagle-import:C0805")
      (libsource (lib "eagle-import") (part "C-EUC0805"))
    )
    (comp (ref "C5")
      (value "100n")
      (footprint "eagle-import:C0805")
      (libsource (lib "eagle-import") (part "C-EUC0805"))
    )
    (comp (ref "C6")
      (value "10n")
      (footprint "eagle-import:C0805")
      (libsource (lib "eagle-import") (part "C-EUC0805"))
    )
    (comp (ref "C7")
      (value "10n")
      (footprint "eagle-import:C0805")
      (libsource (lib "eagle-import") (part "C-EUC0805"))
    )
    (comp (ref "D5")
      (value "ADC088S052")
      (footprint "eagle-import:TSSOP16")
      (fields
        (field (name "ARROW_PART_NUMBER") "ADC088S052CIMT/NOPB")
        (field (name "MOUSER_PART_NUMBER") "926-AD088S052CIMTNPB")
      )
      (libsource (lib "eagle-import") (part "ADC088S052"))
    )
    (comp (ref "H1")
      (value "bl")
      (footprint "eagle-import:CHIPLED_1206")
      (libsource (lib "eagle-import") (part "LEDCHIPLED_1206"))
    )
    (comp (ref "H2")
      (value "gn")
      (footprint "eagle-import:CHIPLED_1206")
      (libsource (lib "eagle-import") (part "LEDCHIPLED_1206"))
    )
    (comp (ref "R1")
      (value "10k")
      (footprint "eagle-import:R0805")
      (libsource (lib "eagle-import") (part "R-EUSR0805"))
    )
    (comp (ref "R3")
      (value "10k")
      (footprint "eagle-import:P160L")
      (libsource (lib "eagle-import") (part "P160L"))
    )
    (comp (ref "R4")
      (value "10k")
      (footprint "eagle-import:P160L")
      (libsource (lib "eagle-import") (part "P160L"))
    )
    (comp (ref "R5")
      (value "10k")
      (footprint "eagle-import:P160L")
      (libsource (lib "eagle-import") (part "P160L"))
    )
    (comp (ref "R6")
      (value "10k")
      (footprint "eagle-import:P160L")
      (libsource (lib "eagle-import") (part "P160L"))
    )
    (comp (ref "R7")
      (value "330R")
      (footprint "eagle-import:R0805")
      (libsource (lib "eagle-import") (part "R-EUSR0805"))
    )
    (comp (ref "R8")
      (value "330R")
      (footprint "eagle-import:R0805")
      (libsource (lib "eagle-import") (part "R-EUSR0805"))
    )
    (comp (ref "R9")
      (value "1M")
      (footprint "eagle-import:R0805")
      (libsource (lib "eagle-import") (part "R-EUSR0805"))
    )
    (comp (ref "R10")
      (value "10k")
      (footprint "eagle-import:P160L")
      (libsource (lib "eagle-import") (part "P160L"))
    )
    (comp (ref "R11")
      (value "10k")
      (footprint "eagle-import:P160L")
      (libsource (lib "eagle-import") (part "P160L"))
    )
    (comp (ref "R12")
      (value "10k")
      (footprint "eagle-import:P160L")
      (libsource (lib "eagle-import") (part "P160L"))
    )
    (comp (ref "R13")
      (value "10k")
      (footprint "eagle-import:P160L")
      (libsource (lib "eagle-import") (part "P160L"))
    )
    (comp (ref "R14")
      (value "56k")
      (footprint "eagle-import:R0805")
      (libsource (lib "eagle-import") (part "R-EUSR0805"))
    )
    (comp (ref "R15")
      (value "56k")
      (footprint "eagle-import:R0805")
      (libsource (lib "eagle-import") (part "R-EUSR0805"))
    )
    (comp (ref "R16")
      (value "56k")
      (footprint "eagle-import:R0805")
      (libsource (lib "eagle-import") (part "R-EUSR0805"))
    )
    (comp (ref "R17")
      (value "56k")
      (footprint "eagle-import:R0805")
      (libsource (lib "eagle-import") (part "R-EUSR0805"))
    )
    (comp (ref "R18")
      (value "56k")
      (footprint "eagle-import:R0805")
      (libsource (lib "eagle-import") (part "R-EUSR0805"))
    )
    (comp (ref "R19")
      (value "56k")
      (footprint "eagle-import:R0805")
      (libsource (lib "eagle-import") (part "R-EUSR0805"))
    )
    (comp (ref "R20")
      (value "56k")
      (footprint "eagle-import:R0805")
      (libsource (lib "eagle-import") (part "R-EUSR0805"))
    )
    (comp (ref "S1")
      (value "TASTE10XX")
      (footprint "eagle-import:B3F-10XX")
      (libsource (lib "eagle-import") (part "TASTE10XX"))
    )
    (comp (ref "S2")
      (value "TASTE10XX")
      (footprint "eagle-import:B3F-10XX")
      (libsource (lib "eagle-import") (part "TASTE10XX"))
    )
    (comp (ref "S3")
      (value "TASTE10XX")
      (footprint "eagle-import:B3F-10XX")
      (libsource (lib "eagle-import") (part "TASTE10XX"))
    )
    (comp (ref "S4")
      (value "TASTE10XX")
      (footprint "eagle-import:B3F-10XX")
      (libsource (lib "eagle-import") (part "TASTE10XX"))
    )
    (comp (ref "S5")
      (value "TASTE10XX")
      (footprint "eagle-import:B3F-10XX")
      (libsource (lib "eagle-import") (part "TASTE10XX"))
    )
    (comp (ref "S6")
      (value "TASTE10XX")
      (footprint "eagle-import:B3F-10XX")
      (libsource (lib "eagle-import") (part "TASTE10XX"))
    )
    (comp (ref "S7")
      (value "TASTE10XX")
      (footprint "eagle-import:B3F-10XX")
      (libsource (lib "eagle-import") (part "TASTE10XX"))
    )
    (comp (ref "S8")
      (value "TASTE10XX")
      (footprint "eagle-import:B3F-10XX")
      (libsource (lib "eagle-import") (part "TASTE10XX"))
    )
    (comp (ref "S9")
      (value "TASTE10XX")
      (footprint "eagle-import:B3F-10XX")
      (libsource (lib "eagle-import") (part "TASTE10XX"))
    )
    (comp (ref "S10")
      (value "TASTE10XX")
      (footprint "eagle-import:B3F-10XX")
      (libsource (lib "eagle-import") (part "TASTE10XX"))
    )
    (comp (ref "S11")
      (value "TASTE10XX")
      (footprint "eagle-import:B3F-10XX")
      (libsource (lib "eagle-import") (part "TASTE10XX"))
    )
    (comp (ref "S12")
      (value "TASTE10XX")
      (footprint "eagle-import:B3F-10XX")
      (libsource (lib "eagle-import") (part "TASTE10XX"))
    )
    (comp (ref "S13")
      (value "TASTE10XX")
      (footprint "eagle-import:B3F-10XX")
      (libsource (lib "eagle-import") (part "TASTE10XX"))
    )
    (comp (ref "S14")
      (value "TASTE10XX")
      (footprint "eagle-import:B3F-10XX")
      (libsource (lib "eagle-import") (part "TASTE10XX"))
    )
    (comp (ref "S15")
      (value "EC11E09244AQ")
      (footprint "eagle-import:EC11")
      (fields (field (name "MOUSER_PART_NUMBER") "688-EC11E09244AQ"))
      (libsource (lib "eagle-import") (part "EC11E09244AQ"))
    )
    (comp (ref "V1")
      (value "NTR4003")
      (footprint "eagle-import:SOT23")
      (libsource (lib "eagle-import") (part "NTR4003"))
    )
  )
  (nets
    (net (code "1") (name "+3V3") (class "Default")
      (node (ref "C1") (pin "1") (pinfunction "1_1") (pintype "passive"))
      (node (ref "C10") (pin "1") (pinfunction "1_1") (pintype "passive"))
      (node (ref "C11") (pin "1") (pinfunction "1_1") (pintype "passive"))
      (node (ref "C13") (pin "1") (pinfunction "1_1") (pintype "passive"))
      (node (ref "C14") (pin "1") (pinfunction "1_1") (pintype "passive"))
      (node (ref "C15") (pin "1") (pinfunction "1_1") (pintype "passive"))
      (node (ref "C16") (pin "1") (pinfunction "1_1") (pintype "passive"))
      (node (ref "C17") (pin "1") (pinfunction "1_1") (pintype "passive"))
      (node (ref "C18") (pin "1") (pinfunction "1_1") (pintype "passive"))
      (node (ref "C19") (pin "1") (pinfunction "1_1") (pintype "passive"))
      (node (ref "C2") (pin "1") (pinfunction "1_1") (pintype "passive"))
      (node (ref "C20") (pin "1") (pinfunction "1_1") (pintype "passive"))
      (node (ref "C3") (pin "1") (pinfunction "1_1") (pintype "passive"))
      (node (ref "C4") (pin "1") (pinfunction "1_1") (pintype "passive"))
      (node (ref "C5") (pin "1") (pinfunction "1_1") (pintype "passive"))
      (node (ref "C8") (pin "1") (pinfunction "1_1") (pintype "passive"))
      (node (ref "C9") (pin "1") (pinfunction "1_1") (pintype "passive"))
      (node (ref "D1") (pin "16") (pinfunction "VCC_16") (pintype "bidirectional"))
      (node (ref "D1") (pin "6") (pinfunction "G1_6") (pintype "bidirectional"))
      (node (ref "D10") (pin "4") (pinfunction "VCC_4") (pintype "power_in"))
      (node (ref "D11") (pin "16") (pinfunction "VCC_16") (pintype "bidirectional"))
      (node (ref "D13") (pin "24") (pinfunction "VDD_24") (pintype "bidirectional"))
      (node (ref "D14") (pin "5") (pinfunction "VCC_5") (pintype "power_in"))
      (node (ref "D15") (pin "24") (pinfunction "VDD_24") (pintype "bidirectional"))
      (node (ref "D16") (pin "5") (pinfunction "VCC_5") (pintype "power_in"))
      (node (ref "D2") (pin "18") (pinfunction "VDD_18") (pintype "bidirectional"))
      (node (ref "D2") (pin "6") (pinfunction "~{RESET}_6") (pintype "bidirectional"))
      (node (ref "D3") (pin "18") (pinfunction "VDD_18") (pintype "bidirectional"))
      (node (ref "D3") (pin "5") (pinfunction "A0_5") (pintype "bidirectional"))
      (node (ref "D3") (pin "6") (pinfunction "~{RESET}_6") (pintype "bidirectional"))
      (node (ref "D4") (pin "5") (pinfunction "VCC_5") (pintype "power_in"))
      (node (ref "D5") (pin "13") (pinfunction "VD_13") (pintype "bidirectional"))
      (node (ref "D5") (pin "2") (pinfunction "VA_2") (pintype "bidirectional"))
      (node (ref "D6") (pin "16") (pinfunction "VCC_16") (pintype "bidirectional"))
      (node (ref "D7") (pin "11") (pinfunction "~{PL}_11") (pintype "input"))
      (node (ref "D7") (pin "16") (pinfunction "VCC_16") (pintype "power_in"))
      (node (ref "D7") (pin "5") (pinfunction "CPU_5") (pintype "input"))
      (node (ref "D8") (pin "4") (pinfunction "VCC_4") (pintype "power_in"))
      (node (ref "D9") (pin "4") (pinfunction "VCC_4") (pintype "power_in"))
      (node (ref "H1") (pin "A") (pinfunction "A_A") (pintype "passive"))
      (node (ref "H14") (pin "A") (pinfunction "A_A") (pintype "passive"))
      (node (ref "H15") (pin "A") (pinfunction "A_A") (pintype "passive"))
      (node (ref "H16") (pin "A") (pinfunction "A_A") (pintype "passive"))
      (node (ref "H17") (pin "A") (pinfunction "A_A") (pintype "passive"))
      (node (ref "H18") (pin "A") (pinfunction "A_A") (pintype "passive"))
      (node (ref "H19") (pin "A") (pinfunction "A_A") (pintype "passive"))
      (node (ref "H2") (pin "A") (pinfunction "A_A") (pintype "passive"))
      (node (ref "H20") (pin "A") (pinfunction "A_A") (pintype "passive"))
      (node (ref "H21") (pin "A") (pinfunction "A_A") (pintype "passive"))
      (node (ref "H22") (pin "A") (pinfunction "A_A") (pintype "passive"))
      (node (ref "H23") (pin "A") (pinfunction "A_A") (pintype "passive"))
      (node (ref "H24") (pin "A") (pinfunction "A_A") (pintype "passive"))
      (node (ref "H25") (pin "A") (pinfunction "A_A") (pintype "passive"))
      (node (ref "H26") (pin "A") (pinfunction "A_A") (pintype "passive"))
      (node (ref "H27") (pin "A") (pinfunction "A_A") (pintype "passive"))
      (node (ref "H28") (pin "A") (pinfunction "A_A") (pintype "passive"))
      (node (ref "H29") (pin "A") (pinfunction "A_A") (pintype "passive"))
      (node (ref "H30") (pin "A") (pinfunction "A_A") (pintype "passive"))
      (node (ref "H31") (pin "A") (pinfunction "A_A") (pintype "passive"))
      (node (ref "H32") (pin "A") (pinfunction "A_A") (pintype "passive"))
      (node (ref "H33") (pin "A") (pinfunction "A_A") (pintype "passive"))
      (node (ref "H34") (pin "A") (pinfunction "A_A") (pintype "passive"))
      (node (ref "H35") (pin "A") (pinfunction "A_A") (pintype "passive"))
      (node (ref "H36") (pin "A") (pinfunction "A_A") (pintype "passive"))
      (node (ref "H37") (pin "A") (pinfunction "A_A") (pintype "passive"))
      (node (ref "H38") (pin "A") (pinfunction "A_A") (pintype "passive"))
      (node (ref "H39") (pin "A") (pinfunction "A_A") (pintype "passive"))
      (node (ref "H40") (pin "A") (pinfunction "A_A") (pintype "passive"))
      (node (ref "H41") (pin "A") (pinfunction "A_A") (pintype "passive"))
      (node (ref "H42") (pin "A") (pinfunction "A_A") (pintype "passive"))
      (node (ref "H43") (pin "A") (pinfunction "A_A") (pintype "passive"))
      (node (ref "H44") (pin "A") (pinfunction "A_A") (pintype "passive"))
      (node (ref "H45") (pin "A") (pinfunction "A_A") (pintype "passive"))
      (node (ref "R1") (pin "2") (pinfunction "2_2") (pintype "passive"))
      (node (ref "R10") (pin "3") (pinfunction "2_3") (pintype "passive"))
      (node (ref "R11") (pin "3") (pinfunction "2_3") (pintype "passive"))
      (node (ref "R12") (pin "3") (pinfunction "2_3") (pintype "passive"))
      (node (ref "R13") (pin "3") (pinfunction "2_3") (pintype "passive"))
      (node (ref "R18") (pin "2") (pinfunction "2_2") (pintype "passive"))
      (node (ref "R19") (pin "2") (pinfunction "2_2") (pintype "passive"))
      (node (ref "R2") (pin "2") (pinfunction "2_2") (pintype "passive"))
      (node (ref "R20") (pin "2") (pinfunction "2_2") (pintype "passive"))
      (node (ref "R21") (pin "2") (pinfunction "2_2") (pintype "passive"))
      (node (ref "R28") (pin "2") (pinfunction "2_2") (pintype "passive"))
      (node (ref "R3") (pin "3") (pinfunction "2_3") (pintype "passive"))
      (node (ref "R4") (pin "3") (pinfunction "2_3") (pintype "passive"))
      (node (ref "R46") (pin "2") (pinfunction "2_2") (pintype "passive"))
      (node (ref "R48") (pin "2") (pinfunction "2_2") (pintype "passive"))
      (node (ref "R5") (pin "3") (pinfunction "2_3") (pintype "passive"))
      (node (ref "R6") (pin "3") (pinfunction "2_3") (pintype "passive"))
      (node (ref "S10") (pin "2") (pinfunction "P1_2") (pintype "passive"))
      (node (ref "S11") (pin "1") (pinfunction "P_1") (pintype "passive"))
      (node (ref "S12") (pin "1") (pinfunction "P_1") (pintype "passive"))
      (node (ref "S13") (pin "2") (pinfunction "P1_2") (pintype "passive"))
      (node (ref "S14") (pin "1") (pinfunction "P_1") (pintype "passive"))
      (node (ref "S2") (pin "1") (pinfunction "P_1") (pintype "passive"))
      (node (ref "S3") (pin "1") (pinfunction "P_1") (pintype "passive"))
      (node (ref "S4") (pin "1") (pinfunction "P_1") (pintype "passive"))
      (node (ref "S5") (pin "1") (pinfunction "P_1") (pintype "passive"))
      (node (ref "S7") (pin "2") (pinfunction "P1_2") (pintype "passive"))
      (node (ref "S8") (pin "2") (pinfunction "P1_2") (pintype "passive"))
      (node (ref "S9") (pin "2") (pinfunction "P1_2") (pintype "passive"))
      (node (ref "X1") (pin "1") (pinfunction "3V3_1") (pintype "power_in"))
      (node (ref "X2") (pin "6") (pinfunction "6_6") (pintype "passive"))
    )
    (net (code "2") (name "+5V") (class "Default")
      (node (ref "C12") (pin "1") (pinfunction "1_1") (pintype "passive"))
      (node (ref "D12") (pin "5") (pinfunction "VCC_5") (pintype "power_in"))
      (node (ref "H10") (pin "2") (pinfunction "VDD_2") (pintype "bidirectional"))
      (node (ref "H3") (pin "2") (pinfunction "VDD_2") (pintype "bidirectional"))
      (node (ref "H4") (pin "2") (pinfunction "VDD_2") (pintype "bidirectional"))
      (node (ref "H5") (pin "2") (pinfunction "VDD_2") (pintype "bidirectional"))
      (node (ref "H6") (pin "2") (pinfunction "VDD_2") (pintype "bidirectional"))
      (node (ref "H7") (pin "2") (pinfunction "VDD_2") (pintype "bidirectional"))
      (node (ref "H8") (pin "2") (pinfunction "VDD_2") (pintype "bidirectional"))
      (node (ref "H9") (pin "2") (pinfunction "VDD_2") (pintype "bidirectional"))
      (node (ref "X1") (pin "19") (pinfunction "5V_19") (pintype "power_in"))
    )
    (net (code "3") (name "7SEG_A") (class "Default")
      (node (ref "D3") (pin "10") (pinfunction "GP0_10") (pintype "bidirectional"))
      (node (ref "R42") (pin "2") (pinfunction "2_2") (pintype "passive"))
    )
    (net (code "4") (name "7SEG_B") (class "Default")
      (node (ref "D3") (pin "11") (pinfunction "GP1_11") (pintype "bidirectional"))
      (node (ref "R41") (pin "2") (pinfunction "2_2") (pintype "passive"))
    )
    (net (code "5") (name "7SEG_C") (class "Default")
      (node (ref "D3") (pin "12") (pinfunction "GP2_12") (pintype "bidirectional"))
      (node (ref "R40") (pin "2") (pinfunction "2_2") (pintype "passive"))
    )
    (net (code "6") (name "7SEG_CE") (class "Default")
      (node (ref "R45") (pin "2") (pinfunction "2_2") (pintype "passive"))
      (node (ref "V28") (pin "1") (pinfunction "G_1") (pintype "passive"))
      (node (ref "X1") (pin "8") (pinfunction "GPIO33/ADC1_CH5_8") (pintype "bidirectional"))
    )
    (net (code "7") (name "7SEG_CH") (class "Default")
      (node (ref "R43") (pin "2") (pinfunction "2_2") (pintype "passive"))
      (node (ref "V26") (pin "1") (pinfunction "G_1") (pintype "passive"))
      (node (ref "X1") (pin "10") (pinfunction "GPIO26/ADC2_CH9/DAC2_10") (pintype "bidirectional"))
    )
    (net (code "8") (name "7SEG_CZ") (class "Default")
      (node (ref "R44") (pin "2") (pinfunction "2_2") (pintype "passive"))
      (node (ref "V27") (pin "1") (pinfunction "G_1") (pintype "passive"))
      (node (ref "X1") (pin "9") (pinfunction "GPIO25/ADC2_CH8/DAC1_9") (pintype "bidirectional"))
    )
    (net (code "9") (name "7SEG_D") (class "Default")
      (node (ref "D3") (pin "13") (pinfunction "GP3_13") (pintype "bidirectional"))
      (node (ref "R39") (pin "2") (pinfunction "2_2") (pintype "passive"))
    )
    (net (code "10") (name "7SEG_DP") (class "Default")
      (node (ref "D3") (pin "17") (pinfunction "GP7_17") (pintype "bidirectional"))
      (node (ref "R35") (pin "2") (pinfunction "2_2") (pintype "passive"))
    )
    (net (code "11") (name "7SEG_E") (class "Default")
      (node (ref "D3") (pin "14") (pinfunction "GP4_14") (pintype "bidirectional"))
      (node (ref "R38") (pin "2") (pinfunction "2_2") (pintype "passive"))
    )
    (net (code "12") (name "7SEG_F") (class "Default")
      (node (ref "D3") (pin "15") (pinfunction "GP5_15") (pintype "bidirectional"))
      (node (ref "R37") (pin "2") (pinfunction "2_2") (pintype "passive"))
    )
    (net (code "13") (name "7SEG_G") (class "Default")
      (node (ref "D3") (pin "16") (pinfunction "GP6_16") (pintype "bidirectional"))
      (node (ref "R36") (pin "2") (pinfunction "2_2") (pintype "passive"))
    )
    (net (code "14") (name "23S08_~{CS}") (class "Default")
      (node (ref "D1") (pin "15") (pinfunction "Y0_15") (pintype "bidirectional"))
      (node (ref "D2") (pin "7") (pinfunction "~{CS}_7") (pintype "bidirectional"))
      (node (ref "D3") (pin "7") (pinfunction "~{CS}_7") (pintype "bidirectional"))
      (node (ref "D4") (pin "1") (pinfunction "~{OE}_1") (pintype "bidirectional"))
      (node (ref "R2") (pin "1") (pinfunction "1_1") (pintype "passive"))
    )
    (net (code "15") (name "088S052_~{CS}") (class "Default")
      (node (ref "D1") (pin "12") (pinfunction "Y3_12") (pintype "bidirectional"))
      (node (ref "D5") (pin "1") (pinfunction "~{CS}_1") (pintype "bidirectional"))
      (node (ref "R1") (pin "1") (pinfunction "1_1") (pintype "passive"))
    )
    (net (code "16") (name "ADC0") (class "Default")
      (node (ref "D5") (pin "4") (pinfunction "IN0_4") (pintype "bidirectional"))
      (node (ref "R3") (pin "2") (pinfunction "3_2") (pintype "passive"))
    )
    (net (code "17") (name "ADC1") (class "Default")
      (node (ref "D5") (pin "5") (pinfunction "IN1_5") (pintype "bidirectional"))
      (node (ref "R4") (pin "2") (pinfunction "3_2") (pintype "passive"))
    )
    (net (code "18") (name "ADC2") (class "Default")
      (node (ref "D5") (pin "6") (pinfunction "IN2_6") (pintype "bidirectional"))
      (node (ref "R5") (pin "2") (pinfunction "3_2") (pintype "passive"))
    )
    (net (code "19") (name "ADC3") (class "Default")
      (node (ref "D5") (pin "7") (pinfunction "IN3_7") (pintype "bidirectional"))
      (node (ref "R6") (pin "2") (pinfunction "3_2") (pintype "passive"))
    )
    (net (code "20") (name "ADC4") (class "Default")
      (node (ref "D5") (pin "8") (pinfunction "IN4_8") (pintype "bidirectional"))
      (node (ref "R10") (pin "2") (pinfunction "3_2") (pintype "passive"))
    )
    (net (code "21") (name "ADC5") (class "Default")
      (node (ref "D5") (pin "9") (pinfunction "IN5_9") (pintype "bidirectional"))
      (node (ref "R11") (pin "2") (pinfunction "3_2") (pintype "passive"))
    )
    (net (code "22") (name "ADC6") (class "Default")
      (node (ref "D5") (pin "10") (pinfunction "IN6_10") (pintype "bidirectional"))
      (node (ref "R12") (pin "2") (pinfunction "3_2") (pintype "passive"))
    )
    (net (code "23") (name "ADC7") (class "Default")
      (node (ref "D5") (pin "11") (pinfunction "IN7_11") (pintype "bidirectional"))
      (node (ref "R13") (pin "2") (pinfunction "3_2") (pintype "passive"))
    )
    (net (code "24") (name "BCK") (class "Default")
      (node (ref "X1") (pin "26") (pinfunction "GPIO4/ADC2_CH0_26") (pintype "bidirectional"))
      (node (ref "X2") (pin "2") (pinfunction "2_2") (pintype "passive"))
    )
    (net (code "25") (name "BPM_DIV_Q0") (class "Default")
      (node (ref "D6") (pin "11") (pinfunction "A_11") (pintype "bidirectional"))
      (node (ref "D9") (pin "9") (pinfunction "Q_9") (pintype "output"))
    )
    (net (code "26") (name "BPM_DIV_Q1") (class "Default")
      (node (ref "D10") (pin "12") (pinfunction "Q_12") (pintype "output"))
      (node (ref "D6") (pin "10") (pinfunction "B_10") (pintype "bidirectional"))
    )
    (net (code "27") (name "BPM_DIV_Q2") (class "Default")
      (node (ref "D10") (pin "9") (pinfunction "Q_9") (pintype "output"))
      (node (ref "D6") (pin "9") (pinfunction "C_9") (pintype "bidirectional"))
    )
    (net (code "28") (name "CLRR") (class "Default")
      (node (ref "D2") (pin "11") (pinfunction "GP1_11") (pintype "bidirectional"))
      (node (ref "R17") (pin "2") (pinfunction "2_2") (pintype "passive"))
      (node (ref "S11") (pin "3") (pinfunction "S_3") (pintype "passive"))
    )
    (net (code "29") (name "DOUT") (class "Default")
      (node (ref "X1") (pin "27") (pinfunction "GPIO16_27") (pintype "bidirectional"))
      (node (ref "X2") (pin "3") (pinfunction "3_3") (pintype "passive"))
    )
    (net (code "30") (name "EC11_A") (class "Default")
      (node (ref "C6") (pin "1") (pinfunction "1_1") (pintype "passive"))
      (node (ref "R18") (pin "1") (pinfunction "1_1") (pintype "passive"))
      (node (ref "S15") (pin "A1") (pinfunction "CW_A1") (pintype "output"))
      (node (ref "X1") (pin "13") (pinfunction "GPIO12/ADC2_CH5/HSPIQ_13") (pintype "bidirectional"))
    )
    (net (code "31") (name "EC11_B") (class "Default")
      (node (ref "C7") (pin "1") (pinfunction "1_1") (pintype "passive"))
      (node (ref "R19") (pin "1") (pinfunction "1_1") (pintype "passive"))
      (node (ref "S15") (pin "B1") (pinfunction "CCW_B1") (pintype "output"))
      (node (ref "X1") (pin "12") (pinfunction "GPIO14/ADC2_CH6/HSCK_12") (pintype "bidirectional"))
    )
    (net (code "32") (name "EC11_SW") (class "Default")
      (node (ref "R20") (pin "1") (pinfunction "1_1") (pintype "passive"))
      (node (ref "S15") (pin "E1") (pinfunction "NO_E1") (pintype "bidirectional"))
      (node (ref "X1") (pin "11") (pinfunction "GPIO27/ADC2_CH7_11") (pintype "bidirectional"))
    )
    (net (code "33") (name "EVENT") (class "Default")
      (node (ref "D2") (pin "10") (pinfunction "GP0_10") (pintype "bidirectional"))
      (node (ref "R16") (pin "2") (pinfunction "2_2") (pintype "passive"))
      (node (ref "R9") (pin "2") (pinfunction "2_2") (pintype "passive"))
      (node (ref "S13") (pin "4") (pinfunction "S1_4") (pintype "passive"))
      (node (ref "V1") (pin "1") (pinfunction "G_1") (pintype "passive"))
    )
    (net (code "34") (name "GATE_DIV_Q0") (class "Default")
      (node (ref "D11") (pin "11") (pinfunction "A_11") (pintype "bidirectional"))
      (node (ref "D8") (pin "9") (pinfunction "Q_9") (pintype "output"))
    )
    (net (code "35") (name "GATE_DIV_Q1") (class "Default")
      (node (ref "D11") (pin "10") (pinfunction "B_10") (pintype "bidirectional"))
      (node (ref "D8") (pin "12") (pinfunction "Q_12") (pintype "output"))
    )
    (net (code "36") (name "GATE_DIV_Q2") (class "Default")
      (node (ref "D11") (pin "9") (pinfunction "C_9") (pintype "bidirectional"))
      (node (ref "D9") (pin "12") (pinfunction "Q_12") (pintype "output"))
    )
    (net (code "37") (name "GND") (class "Default")
      (node (ref "C1") (pin "2") (pinfunction "2_2") (pintype "passive"))
      (node (ref "C10") (pin "2") (pinfunction "2_2") (pintype "passive"))
      (node (ref "C11") (pin "2") (pinfunction "2_2") (pintype "passive"))
      (node (ref "C12") (pin "2") (pinfunction "2_2") (pintype "passive"))
      (node (ref "C13") (pin "2") (pinfunction "2_2") (pintype "passive"))
      (node (ref "C14") (pin "2") (pinfunction "2_2") (pintype "passive"))
      (node (ref "C15") (pin "2") (pinfunction "2_2") (pintype "passive"))
      (node (ref "C16") (pin "2") (pinfunction "2_2") (pintype "passive"))
      (node (ref "C17") (pin "2") (pinfunction "2_2") (pintype "passive"))
      (node (ref "C18") (pin "2") (pinfunction "2_2") (pintype "passive"))
      (node (ref "C19") (pin "2") (pinfunction "2_2") (pintype "passive"))
      (node (ref "C2") (pin "2") (pinfunction "2_2") (pintype "passive"))
      (node (ref "C20") (pin "2") (pinfunction "2_2") (pintype "passive"))
      (node (ref "C3") (pin "2") (pinfunction "2_2") (pintype "passive"))
      (node (ref "C4") (pin "2") (pinfunction "2_2") (pintype "passive"))
      (node (ref "C5") (pin "2") (pinfunction "2_2") (pintype "passive"))
      (node (ref "C6") (pin "2") (pinfunction "2_2") (pintype "passive"))
      (node (ref "C7") (pin "2") (pinfunction "2_2") (pintype "passive"))
      (node (ref "C8") (pin "2") (pinfunction "2_2") (pintype "passive"))
      (node (ref "C9") (pin "2") (pinfunction "2_2") (pintype "passive"))
      (node (ref "D1") (pin "4") (pinfunction "~{G2A}_4") (pintype "bidirectional"))
      (node (ref "D1") (pin "5") (pinfunction "~{G2B}_5") (pintype "bidirectional"))
      (node (ref "D1") (pin "8") (pinfunction "GND_8") (pintype "bidirectional"))
      (node (ref "D10") (pin "11") (pinfunction "GND_11") (pintype "power_in"))
      (node (ref "D11") (pin "7") (pinfunction "~{G}_7") (pintype "bidirectional"))
      (node (ref "D11") (pin "8") (pinfunction "GND_8") (pintype "bidirectional"))
      (node (ref "D12") (pin "1") (pinfunction "~{OE}_1") (pintype "bidirectional"))
      (node (ref "D12") (pin "3") (pinfunction "GND_3") (pintype "power_in"))
      (node (ref "D13") (pin "1") (pinfunction "GND_1") (pintype "bidirectional"))
      (node (ref "D13") (pin "21") (pinfunction "~{OE}/~{DM2}_21") (pintype "bidirectional"))
      (node (ref "D14") (pin "3") (pinfunction "GND_3") (pintype "power_in"))
      (node (ref "D15") (pin "1") (pinfunction "GND_1") (pintype "bidirectional"))
      (node (ref "D15") (pin "21") (pinfunction "~{OE}/~{DM2}_21") (pintype "bidirectional"))
      (node (ref "D16") (pin "3") (pinfunction "GND_3") (pintype "power_in"))
      (node (ref "D2") (pin "4") (pinfunction "A1_4") (pintype "bidirectional"))
      (node (ref "D2") (pin "5") (pinfunction "A0_5") (pintype "bidirectional"))
      (node (ref "D2") (pin "9") (pinfunction "VSS_9") (pintype "bidirectional"))
      (node (ref "D3") (pin "4") (pinfunction "A1_4") (pintype "bidirectional"))
      (node (ref "D3") (pin "9") (pinfunction "VSS_9") (pintype "bidirectional"))
      (node (ref "D4") (pin "3") (pinfunction "GND_3") (pintype "power_in"))
      (node (ref "D5") (pin "12") (pinfunction "DGND_12") (pintype "bidirectional"))
      (node (ref "D5") (pin "3") (pinfunction "AGND_3") (pintype "bidirectional"))
      (node (ref "D6") (pin "7") (pinfunction "~{G}_7") (pintype "bidirectional"))
      (node (ref "D6") (pin "8") (pinfunction "GND_8") (pintype "bidirectional"))
      (node (ref "D7") (pin "14") (pinfunction "MR_14") (pintype "input"))
      (node (ref "D7") (pin "8") (pinfunction "GND_8") (pintype "power_in"))
      (node (ref "D8") (pin "11") (pinfunction "GND_11") (pintype "power_in"))
      (node (ref "D9") (pin "11") (pinfunction "GND_11") (pintype "power_in"))
      (node (ref "H10") (pin "3") (pinfunction "VSS_3") (pintype "bidirectional"))
      (node (ref "H3") (pin "3") (pinfunction "VSS_3") (pintype "bidirectional"))
      (node (ref "H4") (pin "3") (pinfunction "VSS_3") (pintype "bidirectional"))
      (node (ref "H5") (pin "3") (pinfunction "VSS_3") (pintype "bidirectional"))
      (node (ref "H6") (pin "3") (pinfunction "VSS_3") (pintype "bidirectional"))
      (node (ref "H7") (pin "3") (pinfunction "VSS_3") (pintype "bidirectional"))
      (node (ref "H8") (pin "3") (pinfunction "VSS_3") (pintype "bidirectional"))
      (node (ref "H9") (pin "3") (pinfunction "VSS_3") (pintype "bidirectional"))
      (node (ref "R10") (pin "1") (pinfunction "1_1") (pintype "passive"))
      (node (ref "R11") (pin "1") (pinfunction "1_1") (pintype "passive"))
      (node (ref "R12") (pin "1") (pinfunction "1_1") (pintype "passive"))
      (node (ref "R13") (pin "1") (pinfunction "1_1") (pintype "passive"))
      (node (ref "R14") (pin "1") (pinfunction "1_1") (pintype "passive"))
      (node (ref "R15") (pin "1") (pinfunction "1_1") (pintype "passive"))
      (node (ref "R16") (pin "1") (pinfunction "1_1") (pintype "passive"))
      (node (ref "R17") (pin "1") (pinfunction "1_1") (pintype "passive"))
      (node (ref "R22") (pin "1") (pinfunction "1_1") (pintype "passive"))
      (node (ref "R23") (pin "1") (pinfunction "1_1") (pintype "passive"))
      (node (ref "R24") (pin "1") (pinfunction "1_1") (pintype "passive"))
      (node (ref "R25") (pin "1") (pinfunction "1_1") (pintype "passive"))
      (node (ref "R26") (pin "1") (pinfunction "1_1") (pintype "passive"))
      (node (ref "R27") (pin "1") (pinfunction "1_1") (pintype "passive"))
      (node (ref "R29") (pin "1") (pinfunction "1_1") (pintype "passive"))
      (node (ref "R3") (pin "1") (pinfunction "1_1") (pintype "passive"))
      (node (ref "R30") (pin "1") (pinfunction "1_1") (pintype "passive"))
      (node (ref "R31") (pin "1") (pinfunction "1_1") (pintype "passive"))
      (node (ref "R32") (pin "1") (pinfunction "1_1") (pintype "passive"))
      (node (ref "R33") (pin "1") (pinfunction "1_1") (pintype "passive"))
      (node (ref "R34") (pin "1") (pinfunction "1_1") (pintype "passive"))
      (node (ref "R4") (pin "1") (pinfunction "1_1") (pintype "passive"))
      (node (ref "R43") (pin "1") (pinfunction "1_1") (pintype "passive"))
      (node (ref "R44") (pin "1") (pinfunction "1_1") (pintype "passive"))
      (node (ref "R45") (pin "1") (pinfunction "1_1") (pintype "passive"))
      (node (ref "R47") (pin "1") (pinfunction "1_1") (pintype "passive"))
      (node (ref "R49") (pin "1") (pinfunction "1_1") (pintype "passive"))
      (node (ref "R5") (pin "1") (pinfunction "1_1") (pintype "passive"))
      (node (ref "R6") (pin "1") (pinfunction "1_1") (pintype "passive"))
      (node (ref "R8") (pin "1") (pinfunction "1_1") (pintype "passive"))
      (node (ref "R9") (pin "1") (pinfunction "1_1") (pintype "passive"))
      (node (ref "S1") (pin "1") (pinfunction "P_1") (pintype "passive"))
      (node (ref "S15") (pin "C1") (pinfunction "WIPER_C1") (pintype "bidirectional"))
      (node (ref "S15") (pin "D1") (pinfunction "COM_D1") (pintype "bidirectional"))
      (node (ref "S15") (pin "MH1") (pinfunction "MH1_MH1") (pintype "bidirectional"))
      (node (ref "S15") (pin "MH2") (pinfunction "MH2_MH2") (pintype "bidirectional"))
      (node (ref "S6") (pin "1") (pinfunction "P_1") (pintype "passive"))
      (node (ref "V1") (pin "2") (pinfunction "S_2") (pintype "passive"))
      (node (ref "V26") (pin "2") (pinfunction "S_2") (pintype "passive"))
      (node (ref "V27") (pin "2") (pinfunction "S_2") (pintype "passive"))
      (node (ref "V28") (pin "2") (pinfunction "S_2") (pintype "passive"))
      (node (ref "X1") (pin "14") (pinfunction "GND1_14") (pintype "power_in"))
      (node (ref "X1") (pin "32") (pinfunction "GND2_32") (pintype "power_in"))
      (node (ref "X1") (pin "38") (pinfunction "GND3_38") (pintype "power_in"))
      (node (ref "X2") (pin "5") (pinfunction "5_5") (pintype "passive"))
    )
    (net (code "38") (name "LCK") (class "Default")
      (node (ref "X1") (pin "28") (pinfunction "GPIO17_28") (pintype "bidirectional"))
      (node (ref "X2") (pin "4") (pinfunction "4_4") (pintype "passive"))
    )
    (net (code "39") (name "MISO") (class "Default")
      (node (ref "D4") (pin "4") (pinfunction "Y_4") (pintype "bidirectional"))
      (node (ref "D5") (pin "15") (pinfunction "DOUT_15") (pintype "bidirectional"))
      (node (ref "X1") (pin "31") (pinfunction "GPIO19/VSPIQ_31") (pintype "bidirectional"))
    )
    (net (code "40") (name "MOSI") (class "Default")
      (node (ref "D13") (pin "2") (pinfunction "SDI_2") (pintype "bidirectional"))
      (node (ref "D15") (pin "2") (pinfunction "SDI_2") (pintype "bidirectional"))
      (node (ref "D3") (pin "2") (pinfunction "SI_2") (pintype "bidirectional"))
      (node (ref "X1") (pin "37") (pinfunction "GPIO23/VSPID_37") (pintype "bidirectional"))
    )
    (net (code "41") (name "Net-(D2-SO)") (class "Default")
      (node (ref "D2") (pin "3") (pinfunction "SO_3") (pintype "bidirectional"))
      (node (ref "D4") (pin "2") (pinfunction "A_2") (pintype "bidirectional"))
    )
    (net (code "42") (name "Net-(D8B-J)") (class "Default")
      (node (ref "D8") (pin "14") (pinfunction "J_14") (pintype "input"))
      (node (ref "R24") (pin "2") (pinfunction "2_2") (pintype "passive"))
      (node (ref "V7") (pin "C") (pinfunction "C_C") (pintype "passive"))
      (node (ref "V8") (pin "C") (pinfunction "C_C") (pintype "passive"))
    )
    (net (code "43") (name "Net-(D8B-K)") (class "Default")
      (node (ref "D8") (pin "3") (pinfunction "K_3") (pintype "input"))
      (node (ref "R25") (pin "2") (pinfunction "2_2") (pintype "passive"))
      (node (ref "V6") (pin "C") (pinfunction "C_C") (pintype "passive"))
      (node (ref "V9") (pin "C") (pinfunction "C_C") (pintype "passive"))
    )
    (net (code "44") (name "Net-(D8C-J)") (class "Default")
      (node (ref "D8") (pin "7") (pinfunction "J_7") (pintype "input"))
      (node (ref "R22") (pin "2") (pinfunction "2_2") (pintype "passive"))
      (node (ref "V3") (pin "C") (pinfunction "C_C") (pintype "passive"))
      (node (ref "V5") (pin "C") (pinfunction "C_C") (pintype "passive"))
    )
    (net (code "45") (name "Net-(D8C-K)") (class "Default")
      (node (ref "D8") (pin "10") (pinfunction "K_10") (pintype "input"))
      (node (ref "R23") (pin "2") (pinfunction "2_2") (pintype "passive"))
      (node (ref "V2") (pin "C") (pinfunction "C_C") (pintype "passive"))
      (node (ref "V4") (pin "C") (pinfunction "C_C") (pintype "passive"))
    )
    (net (code "46") (name "Net-(D9B-J)") (class "Default")
      (node (ref "D9") (pin "14") (pinfunction "J_14") (pintype "input"))
      (node (ref "R26") (pin "2") (pinfunction "2_2") (pintype "passive"))
      (node (ref "V10") (pin "C") (pinfunction "C_C") (pintype "passive"))
    )
    (net (code "47") (name "Net-(D9B-K)") (class "Default")
      (node (ref "D9") (pin "3") (pinfunction "K_3") (pintype "input"))
      (node (ref "R27") (pin "2") (pinfunction "2_2") (pintype "passive"))
      (node (ref "V11") (pin "C") (pinfunction "C_C") (pintype "passive"))
      (node (ref "V12") (pin "C") (pinfunction "C_C") (pintype "passive"))
      (node (ref "V13") (pin "C") (pinfunction "C_C") (pintype "passive"))
    )
    (net (code "48") (name "Net-(D9C-J)") (class "Default")
      (node (ref "D9") (pin "7") (pinfunction "J_7") (pintype "input"))
      (node (ref "R29") (pin "2") (pinfunction "2_2") (pintype "passive"))
      (node (ref "V15") (pin "C") (pinfunction "C_C") (pintype "passive"))
      (node (ref "V17") (pin "C") (pinfunction "C_C") (pintype "passive"))
    )
    (net (code "49") (name "Net-(D9C-K)") (class "Default")
      (node (ref "D9") (pin "10") (pinfunction "K_10") (pintype "input"))
      (node (ref "R30") (pin "2") (pinfunction "2_2") (pintype "passive"))
      (node (ref "V14") (pin "C") (pinfunction "C_C") (pintype "passive"))
      (node (ref "V16") (pin "C") (pinfunction "C_C") (pintype "passive"))
    )
    (net (code "50") (name "Net-(D10B-J)") (class "Default")
      (node (ref "D10") (pin "14") (pinfunction "J_14") (pintype "input"))
      (node (ref "R31") (pin "2") (pinfunction "2_2") (pintype "passive"))
      (node (ref "V19") (pin "C") (pinfunction "C_C") (pintype "passive"))
      (node (ref "V20") (pin "C") (pinfunction "C_C") (pintype "passive"))
    )
    (net (code "51") (name "Net-(D10B-K)") (class "Default")
      (node (ref "D10") (pin "3") (pinfunction "K_3") (pintype "input"))
      (node (ref "R32") (pin "2") (pinfunction "2_2") (pintype "passive"))
      (node (ref "V18") (pin "C") (pinfunction "C_C") (pintype "passive"))
      (node (ref "V21") (pin "C") (pinfunction "C_C") (pintype "passive"))
    )
    (net (code "52") (name "Net-(D10C-J)") (class "Default")
      (node (ref "D10") (pin "7") (pinfunction "J_7") (pintype "input"))
      (node (ref "R33") (pin "2") (pinfunction "2_2") (pintype "passive"))
      (node (ref "V22") (pin "C") (pinfunction "C_C") (pintype "passive"))
    )
    (net (code "53") (name "Net-(D10C-K)") (class "Default")
      (node (ref "D10") (pin "10") (pinfunction "K_10") (pintype "input"))
      (node (ref "R34") (pin "2") (pinfunction "2_2") (pintype "passive"))
      (node (ref "V23") (pin "C") (pinfunction "C_C") (pintype "passive"))
      (node (ref "V24") (pin "C") (pinfunction "C_C") (pintype "passive"))
      (node (ref "V25") (pin "C") (pinfunction "C_C") (pintype "passive"))
    )
    (net (code "54") (name "Net-(D12A-Y)") (class "Default")
      (node (ref "D12") (pin "4") (pinfunction "Y_4") (pintype "bidirectional"))
      (node (ref "H3") (pin "1") (pinfunction "DI_1") (pintype "bidirectional"))
    )
    (net (code "55") (name "Net-(D13-LE{slash}DM1)") (class "Default")
      (node (ref "D13") (pin "4") (pinfunction "LE/DM1_4") (pintype "bidirectional"))
      (node (ref "D14") (pin "4") (pinfunction "Y_4") (pintype "output"))
      (node (ref "R46") (pin "1") (pinfunction "1_1") (pintype "passive"))
    )
    (net (code "56") (name "Net-(D13-R-EXT)") (class "Default")
      (node (ref "D13") (pin "23") (pinfunction "R-EXT_23") (pintype "bidirectional"))
      (node (ref "R47") (pin "2") (pinfunction "2_2") (pintype "passive"))
    )
    (net (code "57") (name "Net-(D13-~{OUT0})") (class "Default")
      (node (ref "D13") (pin "5") (pinfunction "~{OUT0}_5") (pintype "bidirectional"))
      (node (ref "H14") (pin "C") (pinfunction "C_C") (pintype "passive"))
    )
    (net (code "58") (name "Net-(D13-~{OUT1})") (class "Default")
      (node (ref "D13") (pin "6") (pinfunction "~{OUT1}_6") (pintype "bidirectional"))
      (node (ref "H15") (pin "C") (pinfunction "C_C") (pintype "passive"))
    )
    (net (code "59") (name "Net-(D13-~{OUT2})") (class "Default")
      (node (ref "D13") (pin "7") (pinfunction "~{OUT2}_7") (pintype "bidirectional"))
      (node (ref "H16") (pin "C") (pinfunction "C_C") (pintype "passive"))
    )
    (net (code "60") (name "Net-(D13-~{OUT3})") (class "Default")
      (node (ref "D13") (pin "8") (pinfunction "~{OUT3}_8") (pintype "bidirectional"))
      (node (ref "H17") (pin "C") (pinfunction "C_C") (pintype "passive"))
    )
    (net (code "61") (name "Net-(D13-~{OUT4})") (class "Default")
      (node (ref "D13") (pin "9") (pinfunction "~{OUT4}_9") (pintype "bidirectional"))
      (node (ref "H18") (pin "C") (pinfunction "C_C") (pintype "passive"))
    )
    (net (code "62") (name "Net-(D13-~{OUT5})") (class "Default")
      (node (ref "D13") (pin "10") (pinfunction "~{OUT5}_10") (pintype "bidirectional"))
      (node (ref "H19") (pin "C") (pinfunction "C_C") (pintype "passive"))
    )
    (net (code "63") (name "Net-(D13-~{OUT6})") (class "Default")
      (node (ref "D13") (pin "11") (pinfunction "~{OUT6}_11") (pintype "bidirectional"))
      (node (ref "H20") (pin "C") (pinfunction "C_C") (pintype "passive"))
    )
    (net (code "64") (name "Net-(D13-~{OUT7})") (class "Default")
      (node (ref "D13") (pin "12") (pinfunction "~{OUT7}_12") (pintype "bidirectional"))
      (node (ref "H21") (pin "C") (pinfunction "C_C") (pintype "passive"))
    )
    (net (code "65") (name "Net-(D13-~{OUT8})") (class "Default")
      (node (ref "D13") (pin "13") (pinfunction "~{OUT8}_13") (pintype "bidirectional"))
      (node (ref "H22") (pin "C") (pinfunction "C_C") (pintype "passive"))
    )
    (net (code "66") (name "Net-(D13-~{OUT9})") (class "Default")
      (node (ref "D13") (pin "14") (pinfunction "~{OUT9}_14") (pintype "bidirectional"))
      (node (ref "H23") (pin "C") (pinfunction "C_C") (pintype "passive"))
    )
    (net (code "67") (name "Net-(D13-~{OUT10})") (class "Default")
      (node (ref "D13") (pin "15") (pinfunction "~{OUT10}_15") (pintype "bidirectional"))
      (node (ref "H24") (pin "C") (pinfunction "C_C") (pintype "passive"))
    )
    (net (code "68") (name "Net-(D13-~{OUT11})") (class "Default")
      (node (ref "D13") (pin "16") (pinfunction "~{OUT11}_16") (pintype "bidirectional"))
      (node (ref "H25") (pin "C") (pinfunction "C_C") (pintype "passive"))
    )
    (net (code "69") (name "Net-(D13-~{OUT12})") (class "Default")
      (node (ref "D13") (pin "17") (pinfunction "~{OUT12}_17") (pintype "bidirectional"))
      (node (ref "H26") (pin "C") (pinfunction "C_C") (pintype "passive"))
    )
    (net (code "70") (name "Net-(D13-~{OUT13})") (class "Default")
      (node (ref "D13") (pin "18") (pinfunction "~{OUT13}_18") (pintype "bidirectional"))
      (node (ref "H27") (pin "C") (pinfunction "C_C") (pintype "passive"))
    )
    (net (code "71") (name "Net-(D13-~{OUT14})") (class "Default")
      (node (ref "D13") (pin "19") (pinfunction "~{OUT14}_19") (pintype "bidirectional"))
      (node (ref "H28") (pin "C") (pinfunction "C_C") (pintype "passive"))
    )
    (net (code "72") (name "Net-(D13-~{OUT15})") (class "Default")
      (node (ref "D13") (pin "20") (pinfunction "~{OUT15}_20") (pintype "bidirectional"))
      (node (ref "H29") (pin "C") (pinfunction "C_C") (pintype "passive"))
    )
    (net (code "73") (name "Net-(D15-LE{slash}DM1)") (class "Default")
      (node (ref "D15") (pin "4") (pinfunction "LE/DM1_4") (pintype "bidirectional"))
      (node (ref "D16") (pin "4") (pinfunction "Y_4") (pintype "output"))
      (node (ref "R48") (pin "1") (pinfunction "1_1") (pintype "passive"))
    )
    (net (code "74") (name "Net-(D15-R-EXT)") (class "Default")
      (node (ref "D15") (pin "23") (pinfunction "R-EXT_23") (pintype "bidirectional"))
      (node (ref "R49") (pin "2") (pinfunction "2_2") (pintype "passive"))
    )
    (net (code "75") (name "Net-(D15-~{OUT0})") (class "Default")
      (node (ref "D15") (pin "5") (pinfunction "~{OUT0}_5") (pintype "bidirectional"))
      (node (ref "H30") (pin "K") (pinfunction "C_K") (pintype "passive"))
    )
    (net (code "76") (name "Net-(D15-~{OUT1})") (class "Default")
      (node (ref "D15") (pin "6") (pinfunction "~{OUT1}_6") (pintype "bidirectional"))
      (node (ref "H31") (pin "K") (pinfunction "C_K") (pintype "passive"))
    )
    (net (code "77") (name "Net-(D15-~{OUT2})") (class "Default")
      (node (ref "D15") (pin "7") (pinfunction "~{OUT2}_7") (pintype "bidirectional"))
      (node (ref "H32") (pin "K") (pinfunction "C_K") (pintype "passive"))
    )
    (net (code "78") (name "Net-(D15-~{OUT3})") (class "Default")
      (node (ref "D15") (pin "8") (pinfunction "~{OUT3}_8") (pintype "bidirectional"))
      (node (ref "H33") (pin "K") (pinfunction "C_K") (pintype "passive"))
    )
    (net (code "79") (name "Net-(D15-~{OUT4})") (class "Default")
      (node (ref "D15") (pin "9") (pinfunction "~{OUT4}_9") (pintype "bidirectional"))
      (node (ref "H34") (pin "K") (pinfunction "C_K") (pintype "passive"))
    )
    (net (code "80") (name "Net-(D15-~{OUT5})") (class "Default")
      (node (ref "D15") (pin "10") (pinfunction "~{OUT5}_10") (pintype "bidirectional"))
      (node (ref "H35") (pin "K") (pinfunction "C_K") (pintype "passive"))
    )
    (net (code "81") (name "Net-(D15-~{OUT6})") (class "Default")
      (node (ref "D15") (pin "11") (pinfunction "~{OUT6}_11") (pintype "bidirectional"))
      (node (ref "H36") (pin "K") (pinfunction "C_K") (pintype "passive"))
    )
    (net (code "82") (name "Net-(D15-~{OUT7})") (class "Default")
      (node (ref "D15") (pin "12") (pinfunction "~{OUT7}_12") (pintype "bidirectional"))
      (node (ref "H37") (pin "K") (pinfunction "C_K") (pintype "passive"))
    )
    (net (code "83") (name "Net-(D15-~{OUT8})") (class "Default")
      (node (ref "D15") (pin "13") (pinfunction "~{OUT8}_13") (pintype "bidirectional"))
      (node (ref "H38") (pin "K") (pinfunction "C_K") (pintype "passive"))
    )
    (net (code "84") (name "Net-(D15-~{OUT9})") (class "Default")
      (node (ref "D15") (pin "14") (pinfunction "~{OUT9}_14") (pintype "bidirectional"))
      (node (ref "H39") (pin "K") (pinfunction "C_K") (pintype "passive"))
    )
    (net (code "85") (name "Net-(D15-~{OUT10})") (class "Default")
      (node (ref "D15") (pin "15") (pinfunction "~{OUT10}_15") (pintype "bidirectional"))
      (node (ref "H40") (pin "K") (pinfunction "C_K") (pintype "passive"))
    )
    (net (code "86") (name "Net-(D15-~{OUT11})") (class "Default")
      (node (ref "D15") (pin "16") (pinfunction "~{OUT11}_16") (pintype "bidirectional"))
      (node (ref "H41") (pin "K") (pinfunction "C_K") (pintype "passive"))
    )
    (net (code "87") (name "Net-(D15-~{OUT12})") (class "Default")
      (node (ref "D15") (pin "17") (pinfunction "~{OUT12}_17") (pintype "bidirectional"))
      (node (ref "H42") (pin "K") (pinfunction "C_K") (pintype "passive"))
    )
    (net (code "88") (name "Net-(D15-~{OUT13})") (class "Default")
      (node (ref "D15") (pin "18") (pinfunction "~{OUT13}_18") (pintype "bidirectional"))
      (node (ref "H43") (pin "K") (pinfunction "C_K") (pintype "passive"))
    )
    (net (code "89") (name "Net-(D15-~{OUT14})") (class "Default")
      (node (ref "D15") (pin "19") (pinfunction "~{OUT14}_19") (pintype "bidirectional"))
      (node (ref "H44") (pin "K") (pinfunction "C_K") (pintype "passive"))
    )
    (net (code "90") (name "Net-(D15-~{OUT15})") (class "Default")
      (node (ref "D15") (pin "20") (pinfunction "~{OUT15}_20") (pintype "bidirectional"))
      (node (ref "H45") (pin "K") (pinfunction "C_K") (pintype "passive"))
    )
    (net (code "91") (name "Net-(H1-PadC)") (class "Default")
      (node (ref "H1") (pin "C") (pinfunction "C_C") (pintype "passive"))
      (node (ref "R7") (pin "2") (pinfunction "2_2") (pintype "passive"))
    )
    (net (code "92") (name "Net-(H2-PadC)") (class "Default")
      (node (ref "H2") (pin "C") (pinfunction "C_C") (pintype "passive"))
      (node (ref "R8") (pin "2") (pinfunction "2_2") (pintype "passive"))
    )
    (net (code "93") (name "Net-(H3-DO)") (class "Default")
      (node (ref "H3") (pin "4") (pinfunction "DO_4") (pintype "bidirectional"))
      (node (ref "H5") (pin "1") (pinfunction "DI_1") (pintype "bidirectional"))
    )
    (net (code "94") (name "Net-(H4-DI)") (class "Default")
      (node (ref "H4") (pin "1") (pinfunction "DI_1") (pintype "bidirectional"))
      (node (ref "H9") (pin "4") (pinfunction "DO_4") (pintype "bidirectional"))
    )
    (net (code "95") (name "Net-(H4-DO)") (class "Default")
      (node (ref "H4") (pin "4") (pinfunction "DO_4") (pintype "bidirectional"))
      (node (ref "H6") (pin "1") (pinfunction "DI_1") (pintype "bidirectional"))
    )
    (net (code "96") (name "Net-(H5-DO)") (class "Default")
      (node (ref "H5") (pin "4") (pinfunction "DO_4") (pintype "bidirectional"))
      (node (ref "H7") (pin "1") (pinfunction "DI_1") (pintype "bidirectional"))
    )
    (net (code "97") (name "Net-(H6-DO)") (class "Default")
      (node (ref "H6") (pin "4") (pinfunction "DO_4") (pintype "bidirectional"))
      (node (ref "H8") (pin "1") (pinfunction "DI_1") (pintype "bidirectional"))
    )
    (net (code "98") (name "Net-(H7-DO)") (class "Default")
      (node (ref "H7") (pin "4") (pinfunction "DO_4") (pintype "bidirectional"))
      (node (ref "H9") (pin "1") (pinfunction "DI_1") (pintype "bidirectional"))
    )
    (net (code "99") (name "Net-(H10-DI)") (class "Default")
      (node (ref "H10") (pin "1") (pinfunction "DI_1") (pintype "bidirectional"))
      (node (ref "H8") (pin "4") (pinfunction "DO_4") (pintype "bidirectional"))
    )
    (net (code "100") (name "Net-(H11-PadA)") (class "Default")
      (node (ref "H11") (pin "A") (pinfunction "A_A") (pintype "passive"))
      (node (ref "H12") (pin "A") (pinfunction "A_A") (pintype "passive"))
      (node (ref "H13") (pin "A") (pinfunction "A_A") (pintype "passive"))
      (node (ref "R42") (pin "1") (pinfunction "1_1") (pintype "passive"))
    )
    (net (code "101") (name "Net-(H11-PadB)") (class "Default")
      (node (ref "H11") (pin "B") (pinfunction "B_B") (pintype "passive"))
      (node (ref "H12") (pin "B") (pinfunction "B_B") (pintype "passive"))
      (node (ref "H13") (pin "B") (pinfunction "B_B") (pintype "passive"))
      (node (ref "R41") (pin "1") (pinfunction "1_1") (pintype "passive"))
    )
    (net (code "102") (name "Net-(H11-PadC)") (class "Default")
      (node (ref "H11") (pin "C") (pinfunction "C_C") (pintype "passive"))
      (node (ref "H12") (pin "C") (pinfunction "C_C") (pintype "passive"))
      (node (ref "H13") (pin "C") (pinfunction "C_C") (pintype "passive"))
      (node (ref "R40") (pin "1") (pinfunction "1_1") (pintype "passive"))
    )
    (net (code "103") (name "Net-(H11-PadD)") (class "Default")
      (node (ref "H11") (pin "D") (pinfunction "D_D") (pintype "passive"))
      (node (ref "H12") (pin "D") (pinfunction "D_D") (pintype "passive"))
      (node (ref "H13") (pin "D") (pinfunction "D_D") (pintype "passive"))
      (node (ref "R39") (pin "1") (pinfunction "1_1") (pintype "passive"))
    )
    (net (code "104") (name "Net-(H11-PadDP)") (class "Default")
      (node (ref "H11") (pin "DP") (pinfunction "DP_DP") (pintype "passive"))
      (node (ref "H12") (pin "DP") (pinfunction "DP_DP") (pintype "passive"))
      (node (ref "H13") (pin "DP") (pinfunction "DP_DP") (pintype "passive"))
      (node (ref "R35") (pin "1") (pinfunction "1_1") (pintype "passive"))
    )
    (net (code "105") (name "Net-(H11-PadE)") (class "Default")
      (node (ref "H11") (pin "E") (pinfunction "E_E") (pintype "passive"))
      (node (ref "H12") (pin "E") (pinfunction "E_E") (pintype "passive"))
      (node (ref "H13") (pin "E") (pinfunction "E_E") (pintype "passive"))
      (node (ref "R38") (pin "1") (pinfunction "1_1") (pintype "passive"))
    )
    (net (code "106") (name "Net-(H11-PadF)") (class "Default")
      (node (ref "H11") (pin "F") (pinfunction "F_F") (pintype "passive"))
      (node (ref "H12") (pin "F") (pinfunction "F_F") (pintype "passive"))
      (node (ref "H13") (pin "F") (pinfunction "F_F") (pintype "passive"))
      (node (ref "R37") (pin "1") (pinfunction "1_1") (pintype "passive"))
    )
    (net (code "107") (name "Net-(H11-PadG)") (class "Default")
      (node (ref "H11") (pin "G") (pinfunction "G_G") (pintype "passive"))
      (node (ref "H12") (pin "G") (pinfunction "G_G") (pintype "passive"))
      (node (ref "H13") (pin "G") (pinfunction "G_G") (pintype "passive"))
      (node (ref "R36") (pin "1") (pinfunction "1_1") (pintype "passive"))
    )
    (net (code "108") (name "Net-(V1-D)") (class "Default")
      (node (ref "R7") (pin "1") (pinfunction "1_1") (pintype "passive"))
      (node (ref "V1") (pin "3") (pinfunction "D_3") (pintype "passive"))
    )
    (net (code "109") (name "Net-(V26-D)") (class "Default")
      (node (ref "H11") (pin "CC1") (pinfunction "CC_CC1") (pintype "passive"))
      (node (ref "H11") (pin "CC2") (pinfunction "CC_CC2") (pintype "passive"))
      (node (ref "V26") (pin "3") (pinfunction "D_3") (pintype "passive"))
    )
    (net (code "110") (name "Net-(V27-D)") (class "Default")
      (node (ref "H12") (pin "CC1") (pinfunction "CC_CC1") (pintype "passive"))
      (node (ref "H12") (pin "CC2") (pinfunction "CC_CC2") (pintype "passive"))
      (node (ref "V27") (pin "3") (pinfunction "D_3") (pintype "passive"))
    )
    (net (code "111") (name "Net-(V28-D)") (class "Default")
      (node (ref "H13") (pin "CC1") (pinfunction "CC_CC1") (pintype "passive"))
      (node (ref "H13") (pin "CC2") (pinfunction "CC_CC2") (pintype "passive"))
      (node (ref "V28") (pin "3") (pinfunction "D_3") (pintype "passive"))
    )
    (net (code "112") (name "PAUSE_CNT") (class "Default")
      (node (ref "D2") (pin "13") (pinfunction "GP3_13") (pintype "bidirectional"))
      (node (ref "R14") (pin "2") (pinfunction "2_2") (pintype "passive"))
      (node (ref "S12") (pin "3") (pinfunction "S_3") (pintype "passive"))
    )
    (net (code "113") (name "PL_DIN") (class "Default")
      (node (ref "D12") (pin "2") (pinfunction "A_2") (pintype "bidirectional"))
      (node (ref "X1") (pin "15") (pinfunction "GPIO13/ADC2_CH4/HSPID_15") (pintype "bidirectional"))
    )
    (net (code "114") (name "PS_BPM") (class "Default")
      (node (ref "D6") (pin "5") (pinfunction "Y_5") (pintype "bidirectional"))
      (node (ref "X1") (pin "6") (pinfunction "GPIO35/ADC1_CH7_6") (pintype "input"))
    )
    (net (code "115") (name "PS_GATE") (class "Default")
      (node (ref "D11") (pin "5") (pinfunction "Y_5") (pintype "bidirectional"))
      (node (ref "X1") (pin "5") (pinfunction "GPIO34/ADC1_CH6_5") (pintype "input"))
    )
    (net (code "116") (name "Q0") (class "Default")
      (node (ref "D11") (pin "3") (pinfunction "D1_3") (pintype "bidirectional"))
      (node (ref "D6") (pin "3") (pinfunction "D1_3") (pintype "bidirectional"))
      (node (ref "D7") (pin "3") (pinfunction "Q0_3") (pintype "output"))
    )
    (net (code "117") (name "Q0_SW_BD") (class "Default")
      (node (ref "S2") (pin "3") (pinfunction "S_3") (pintype "passive"))
      (node (ref "V17") (pin "A") (pinfunction "A_A") (pintype "passive"))
      (node (ref "V21") (pin "A") (pinfunction "A_A") (pintype "passive"))
      (node (ref "V25") (pin "A") (pinfunction "A_A") (pintype "passive"))
    )
    (net (code "118") (name "Q0_SW_GD") (class "Default")
      (node (ref "S7") (pin "4") (pinfunction "S1_4") (pintype "passive"))
      (node (ref "V13") (pin "A") (pinfunction "A_A") (pintype "passive"))
      (node (ref "V5") (pin "A") (pinfunction "A_A") (pintype "passive"))
      (node (ref "V9") (pin "A") (pinfunction "A_A") (pintype "passive"))
    )
    (net (code "119") (name "Q1") (class "Default")
      (node (ref "D11") (pin "2") (pinfunction "D2_2") (pintype "bidirectional"))
      (node (ref "D6") (pin "2") (pinfunction "D2_2") (pintype "bidirectional"))
      (node (ref "D7") (pin "2") (pinfunction "Q1_2") (pintype "output"))
    )
    (net (code "120") (name "Q1_SW_BD") (class "Default")
      (node (ref "S3") (pin "3") (pinfunction "S_3") (pintype "passive"))
      (node (ref "V16") (pin "A") (pinfunction "A_A") (pintype "passive"))
      (node (ref "V20") (pin "A") (pinfunction "A_A") (pintype "passive"))
      (node (ref "V24") (pin "A") (pinfunction "A_A") (pintype "passive"))
    )
    (net (code "121") (name "Q1_SW_GD") (class "Default")
      (node (ref "S8") (pin "4") (pinfunction "S1_4") (pintype "passive"))
      (node (ref "V12") (pin "A") (pinfunction "A_A") (pintype "passive"))
      (node (ref "V4") (pin "A") (pinfunction "A_A") (pintype "passive"))
      (node (ref "V8") (pin "A") (pinfunction "A_A") (pintype "passive"))
    )
    (net (code "122") (name "Q2") (class "Default")
      (node (ref "D11") (pin "1") (pinfunction "D3_1") (pintype "bidirectional"))
      (node (ref "D6") (pin "1") (pinfunction "D3_1") (pintype "bidirectional"))
      (node (ref "D7") (pin "6") (pinfunction "Q2_6") (pintype "output"))
    )
    (net (code "123") (name "Q2_SW_BD") (class "Default")
      (node (ref "S4") (pin "3") (pinfunction "S_3") (pintype "passive"))
      (node (ref "V15") (pin "A") (pinfunction "A_A") (pintype "passive"))
      (node (ref "V19") (pin "A") (pinfunction "A_A") (pintype "passive"))
      (node (ref "V23") (pin "A") (pinfunction "A_A") (pintype "passive"))
    )
    (net (code "124") (name "Q2_SW_GD") (class "Default")
      (node (ref "S9") (pin "4") (pinfunction "S1_4") (pintype "passive"))
      (node (ref "V11") (pin "A") (pinfunction "A_A") (pintype "passive"))
      (node (ref "V3") (pin "A") (pinfunction "A_A") (pintype "passive"))
      (node (ref "V7") (pin "A") (pinfunction "A_A") (pintype "passive"))
    )
    (net (code "125") (name "Q3") (class "Default")
      (node (ref "D11") (pin "15") (pinfunction "D4_15") (pintype "bidirectional"))
      (node (ref "D6") (pin "15") (pinfunction "D4_15") (pintype "bidirectional"))
      (node (ref "D7") (pin "7") (pinfunction "Q3_7") (pintype "output"))
    )
    (net (code "126") (name "Q3_SW_BD") (class "Default")
      (node (ref "S5") (pin "3") (pinfunction "S_3") (pintype "passive"))
      (node (ref "V14") (pin "A") (pinfunction "A_A") (pintype "passive"))
      (node (ref "V18") (pin "A") (pinfunction "A_A") (pintype "passive"))
      (node (ref "V22") (pin "A") (pinfunction "A_A") (pintype "passive"))
    )
    (net (code "127") (name "Q3_SW_GD") (class "Default")
      (node (ref "S10") (pin "4") (pinfunction "S1_4") (pintype "passive"))
      (node (ref "V10") (pin "A") (pinfunction "A_A") (pintype "passive"))
      (node (ref "V2") (pin "A") (pinfunction "A_A") (pintype "passive"))
      (node (ref "V6") (pin "A") (pinfunction "A_A") (pintype "passive"))
    )
    (net (code "128") (name "RESET_CNT") (class "Default")
      (node (ref "D2") (pin "12") (pinfunction "GP2_12") (pintype "bidirectional"))
      (node (ref "R15") (pin "2") (pinfunction "2_2") (pintype "passive"))
      (node (ref "S14") (pin "3") (pinfunction "S_3") (pintype "passive"))
    )
    (net (code "129") (name "SCK") (class "Default")
      (node (ref "D13") (pin "3") (pinfunction "CLK_3") (pintype "bidirectional"))
      (node (ref "D15") (pin "3") (pinfunction "CLK_3") (pintype "bidirectional"))
      (node (ref "D2") (pin "1") (pinfunction "SCK_1") (pintype "bidirectional"))
      (node (ref "D3") (pin "1") (pinfunction "SCK_1") (pintype "bidirectional"))
      (node (ref "D5") (pin "16") (pinfunction "SCLK_16") (pintype "bidirectional"))
      (node (ref "X1") (pin "30") (pinfunction "GPIO18/VCLK_30") (pintype "bidirectional"))
    )
    (net (code "130") (name "SRC_BPM") (class "Default")
      (node (ref "D10") (pin "1") (pinfunction "~{CLK}_1") (pintype "input"))
      (node (ref "D10") (pin "5") (pinfunction "~{CLK}_5") (pintype "input"))
      (node (ref "D11") (pin "4") (pinfunction "D0_4") (pintype "bidirectional"))
      (node (ref "D6") (pin "4") (pinfunction "D0_4") (pintype "bidirectional"))
      (node (ref "D7") (pin "4") (pinfunction "CPD_4") (pintype "input"))
      (node (ref "D8") (pin "1") (pinfunction "~{CLK}_1") (pintype "input"))
      (node (ref "D8") (pin "5") (pinfunction "~{CLK}_5") (pintype "input"))
      (node (ref "D9") (pin "1") (pinfunction "~{CLK}_1") (pintype "input"))
      (node (ref "D9") (pin "5") (pinfunction "~{CLK}_5") (pintype "input"))
      (node (ref "X1") (pin "7") (pinfunction "GPIO32/ADC1_CH4_7") (pintype "bidirectional"))
    )
    (net (code "131") (name "SRC_SW_BD") (class "Default")
      (node (ref "D10") (pin "2") (pinfunction "~{CLR}_2") (pintype "input"))
      (node (ref "D10") (pin "6") (pinfunction "~{CLR}_6") (pintype "input"))
      (node (ref "D9") (pin "6") (pinfunction "~{CLR}_6") (pintype "input"))
      (node (ref "R28") (pin "1") (pinfunction "1_1") (pintype "passive"))
      (node (ref "S1") (pin "3") (pinfunction "S_3") (pintype "passive"))
    )
    (net (code "132") (name "SRC_SW_GD") (class "Default")
      (node (ref "D8") (pin "2") (pinfunction "~{CLR}_2") (pintype "input"))
      (node (ref "D8") (pin "6") (pinfunction "~{CLR}_6") (pintype "input"))
      (node (ref "D9") (pin "2") (pinfunction "~{CLR}_2") (pintype "input"))
      (node (ref "R21") (pin "1") (pinfunction "1_1") (pintype "passive"))
      (node (ref "S6") (pin "3") (pinfunction "S_3") (pintype "passive"))
    )
    (net (code "133") (name "STP_LE_K") (class "Default")
      (node (ref "D1") (pin "13") (pinfunction "Y2_13") (pintype "bidirectional"))
      (node (ref "D14") (pin "2") (pinfunction "A_2") (pintype "input"))
    )
    (net (code "134") (name "STP_LE_S") (class "Default")
      (node (ref "D1") (pin "14") (pinfunction "Y1_14") (pintype "bidirectional"))
      (node (ref "D16") (pin "2") (pinfunction "A_2") (pintype "input"))
    )
    (net (code "135") (name "unconnected-(D1-Y4-Pad11)") (class "Default")
      (node (ref "D1") (pin "11") (pinfunction "Y4_11") (pintype "bidirectional"))
    )
    (net (code "136") (name "unconnected-(D1-Y5-Pad10)") (class "Default")
      (node (ref "D1") (pin "10") (pinfunction "Y5_10") (pintype "bidirectional"))
    )
    (net (code "137") (name "unconnected-(D1-Y6-Pad9)") (class "Default")
      (node (ref "D1") (pin "9") (pinfunction "Y6_9") (pintype "bidirectional"))
    )
    (net (code "138") (name "unconnected-(D1-Y7-Pad7)") (class "Default")
      (node (ref "D1") (pin "7") (pinfunction "Y7_7") (pintype "bidirectional"))
    )
    (net (code "139") (name "unconnected-(D2-GP4-Pad14)") (class "Default")
      (node (ref "D2") (pin "14") (pinfunction "GP4_14") (pintype "bidirectional"))
    )
    (net (code "140") (name "unconnected-(D2-GP5-Pad15)") (class "Default")
      (node (ref "D2") (pin "15") (pinfunction "GP5_15") (pintype "bidirectional"))
    )
    (net (code "141") (name "unconnected-(D2-GP6-Pad16)") (class "Default")
      (node (ref "D2") (pin "16") (pinfunction "GP6_16") (pintype "bidirectional"))
    )
    (net (code "142") (name "unconnected-(D2-GP7-Pad17)") (class "Default")
      (node (ref "D2") (pin "17") (pinfunction "GP7_17") (pintype "bidirectional"))
    )
    (net (code "143") (name "unconnected-(D2-INT-Pad8)") (class "Default")
      (node (ref "D2") (pin "8") (pinfunction "INT_8") (pintype "bidirectional"))
    )
    (net (code "144") (name "unconnected-(D2-SI-Pad2)") (class "Default")
      (node (ref "D2") (pin "2") (pinfunction "SI_2") (pintype "bidirectional"))
    )
    (net (code "145") (name "unconnected-(D3-INT-Pad8)") (class "Default")
      (node (ref "D3") (pin "8") (pinfunction "INT_8") (pintype "bidirectional"))
    )
    (net (code "146") (name "unconnected-(D3-SO-Pad3)") (class "Default")
      (node (ref "D3") (pin "3") (pinfunction "SO_3") (pintype "bidirectional"))
    )
    (net (code "147") (name "unconnected-(D5-DIN-Pad14)") (class "Default")
      (node (ref "D5") (pin "14") (pinfunction "DIN_14") (pintype "bidirectional"))
    )
    (net (code "148") (name "unconnected-(D6-D5-Pad14)") (class "Default")
      (node (ref "D6") (pin "14") (pinfunction "D5_14") (pintype "bidirectional"))
    )
    (net (code "149") (name "unconnected-(D6-D6-Pad13)") (class "Default")
      (node (ref "D6") (pin "13") (pinfunction "D6_13") (pintype "bidirectional"))
    )
    (net (code "150") (name "unconnected-(D6-D7-Pad12)") (class "Default")
      (node (ref "D6") (pin "12") (pinfunction "D7_12") (pintype "bidirectional"))
    )
    (net (code "151") (name "unconnected-(D6-W-Pad6)") (class "Default")
      (node (ref "D6") (pin "6") (pinfunction "W_6") (pintype "bidirectional"))
    )
    (net (code "152") (name "unconnected-(D7B-D0-Pad15)") (class "Default")
      (node (ref "D7") (pin "15") (pinfunction "D0_15") (pintype "input"))
    )
    (net (code "153") (name "unconnected-(D7B-D1-Pad1)") (class "Default")
      (node (ref "D7") (pin "1") (pinfunction "D1_1") (pintype "input"))
    )
    (net (code "154") (name "unconnected-(D7B-D2-Pad10)") (class "Default")
      (node (ref "D7") (pin "10") (pinfunction "D2_10") (pintype "input"))
    )
    (net (code "155") (name "unconnected-(D7B-D3-Pad9)") (class "Default")
      (node (ref "D7") (pin "9") (pinfunction "D3_9") (pintype "input"))
    )
    (net (code "156") (name "unconnected-(D7B-~{TCD}-Pad13)") (class "Default")
      (node (ref "D7") (pin "13") (pinfunction "~{TCD}_13") (pintype "output"))
    )
    (net (code "157") (name "unconnected-(D7B-~{TCU}-Pad12)") (class "Default")
      (node (ref "D7") (pin "12") (pinfunction "~{TCU}_12") (pintype "output"))
    )
    (net (code "158") (name "unconnected-(D8B-~{Q}-Pad13)") (class "Default")
      (node (ref "D8") (pin "13") (pinfunction "~{Q}_13") (pintype "output"))
    )
    (net (code "159") (name "unconnected-(D8C-~{Q}-Pad8)") (class "Default")
      (node (ref "D8") (pin "8") (pinfunction "~{Q}_8") (pintype "output"))
    )
    (net (code "160") (name "unconnected-(D9B-~{Q}-Pad13)") (class "Default")
      (node (ref "D9") (pin "13") (pinfunction "~{Q}_13") (pintype "output"))
    )
    (net (code "161") (name "unconnected-(D9C-~{Q}-Pad8)") (class "Default")
      (node (ref "D9") (pin "8") (pinfunction "~{Q}_8") (pintype "output"))
    )
    (net (code "162") (name "unconnected-(D10B-~{Q}-Pad13)") (class "Default")
      (node (ref "D10") (pin "13") (pinfunction "~{Q}_13") (pintype "output"))
    )
    (net (code "163") (name "unconnected-(D10C-~{Q}-Pad8)") (class "Default")
      (node (ref "D10") (pin "8") (pinfunction "~{Q}_8") (pintype "output"))
    )
    (net (code "164") (name "unconnected-(D11-D5-Pad14)") (class "Default")
      (node (ref "D11") (pin "14") (pinfunction "D5_14") (pintype "bidirectional"))
    )
    (net (code "165") (name "unconnected-(D11-D6-Pad13)") (class "Default")
      (node (ref "D11") (pin "13") (pinfunction "D6_13") (pintype "bidirectional"))
    )
    (net (code "166") (name "unconnected-(D11-D7-Pad12)") (class "Default")
      (node (ref "D11") (pin "12") (pinfunction "D7_12") (pintype "bidirectional"))
    )
    (net (code "167") (name "unconnected-(D11-W-Pad6)") (class "Default")
      (node (ref "D11") (pin "6") (pinfunction "W_6") (pintype "bidirectional"))
    )
    (net (code "168") (name "unconnected-(D13-SDO-Pad22)") (class "Default")
      (node (ref "D13") (pin "22") (pinfunction "SDO_22") (pintype "bidirectional"))
    )
    (net (code "169") (name "unconnected-(D15-SDO-Pad22)") (class "Default")
      (node (ref "D15") (pin "22") (pinfunction "SDO_22") (pintype "bidirectional"))
    )
    (net (code "170") (name "unconnected-(H10-DO-Pad4)") (class "Default")
      (node (ref "H10") (pin "4") (pinfunction "DO_4") (pintype "bidirectional"))
    )
    (net (code "171") (name "unconnected-(S1-P1-Pad2)") (class "Default")
      (node (ref "S1") (pin "2") (pinfunction "P1_2") (pintype "passive"))
    )
    (net (code "172") (name "unconnected-(S1-S1-Pad4)") (class "Default")
      (node (ref "S1") (pin "4") (pinfunction "S1_4") (pintype "passive"))
    )
    (net (code "173") (name "unconnected-(S2-P1-Pad2)") (class "Default")
      (node (ref "S2") (pin "2") (pinfunction "P1_2") (pintype "passive"))
    )
    (net (code "174") (name "unconnected-(S2-S1-Pad4)") (class "Default")
      (node (ref "S2") (pin "4") (pinfunction "S1_4") (pintype "passive"))
    )
    (net (code "175") (name "unconnected-(S3-P1-Pad2)") (class "Default")
      (node (ref "S3") (pin "2") (pinfunction "P1_2") (pintype "passive"))
    )
    (net (code "176") (name "unconnected-(S3-S1-Pad4)") (class "Default")
      (node (ref "S3") (pin "4") (pinfunction "S1_4") (pintype "passive"))
    )
    (net (code "177") (name "unconnected-(S4-P1-Pad2)") (class "Default")
      (node (ref "S4") (pin "2") (pinfunction "P1_2") (pintype "passive"))
    )
    (net (code "178") (name "unconnected-(S4-S1-Pad4)") (class "Default")
      (node (ref "S4") (pin "4") (pinfunction "S1_4") (pintype "passive"))
    )
    (net (code "179") (name "unconnected-(S5-P1-Pad2)") (class "Default")
      (node (ref "S5") (pin "2") (pinfunction "P1_2") (pintype "passive"))
    )
    (net (code "180") (name "unconnected-(S5-S1-Pad4)") (class "Default")
      (node (ref "S5") (pin "4") (pinfunction "S1_4") (pintype "passive"))
    )
    (net (code "181") (name "unconnected-(S6-P1-Pad2)") (class "Default")
      (node (ref "S6") (pin "2") (pinfunction "P1_2") (pintype "passive"))
    )
    (net (code "182") (name "unconnected-(S6-S1-Pad4)") (class "Default")
      (node (ref "S6") (pin "4") (pinfunction "S1_4") (pintype "passive"))
    )
    (net (code "183") (name "unconnected-(S7-P-Pad1)") (class "Default")
      (node (ref "S7") (pin "1") (pinfunction "P_1") (pintype "passive"))
    )
    (net (code "184") (name "unconnected-(S7-S-Pad3)") (class "Default")
      (node (ref "S7") (pin "3") (pinfunction "S_3") (pintype "passive"))
    )
    (net (code "185") (name "unconnected-(S8-P-Pad1)") (class "Default")
      (node (ref "S8") (pin "1") (pinfunction "P_1") (pintype "passive"))
    )
    (net (code "186") (name "unconnected-(S8-S-Pad3)") (class "Default")
      (node (ref "S8") (pin "3") (pinfunction "S_3") (pintype "passive"))
    )
    (net (code "187") (name "unconnected-(S9-P-Pad1)") (class "Default")
      (node (ref "S9") (pin "1") (pinfunction "P_1") (pintype "passive"))
    )
    (net (code "188") (name "unconnected-(S9-S-Pad3)") (class "Default")
      (node (ref "S9") (pin "3") (pinfunction "S_3") (pintype "passive"))
    )
    (net (code "189") (name "unconnected-(S10-P-Pad1)") (class "Default")
      (node (ref "S10") (pin "1") (pinfunction "P_1") (pintype "passive"))
    )
    (net (code "190") (name "unconnected-(S10-S-Pad3)") (class "Default")
      (node (ref "S10") (pin "3") (pinfunction "S_3") (pintype "passive"))
    )
    (net (code "191") (name "unconnected-(S11-P1-Pad2)") (class "Default")
      (node (ref "S11") (pin "2") (pinfunction "P1_2") (pintype "passive"))
    )
    (net (code "192") (name "unconnected-(S11-S1-Pad4)") (class "Default")
      (node (ref "S11") (pin "4") (pinfunction "S1_4") (pintype "passive"))
    )
    (net (code "193") (name "unconnected-(S12-P1-Pad2)") (class "Default")
      (node (ref "S12") (pin "2") (pinfunction "P1_2") (pintype "passive"))
    )
    (net (code "194") (name "unconnected-(S12-S1-Pad4)") (class "Default")
      (node (ref "S12") (pin "4") (pinfunction "S1_4") (pintype "passive"))
    )
    (net (code "195") (name "unconnected-(S13-P-Pad1)") (class "Default")
      (node (ref "S13") (pin "1") (pinfunction "P_1") (pintype "passive"))
    )
    (net (code "196") (name "unconnected-(S13-S-Pad3)") (class "Default")
      (node (ref "S13") (pin "3") (pinfunction "S_3") (pintype "passive"))
    )
    (net (code "197") (name "unconnected-(S14-P1-Pad2)") (class "Default")
      (node (ref "S14") (pin "2") (pinfunction "P1_2") (pintype "passive"))
    )
    (net (code "198") (name "unconnected-(S14-S1-Pad4)") (class "Default")
      (node (ref "S14") (pin "4") (pinfunction "S1_4") (pintype "passive"))
    )
    (net (code "199") (name "unconnected-(X1-CLK-Pad20)") (class "Default")
      (node (ref "X1") (pin "20") (pinfunction "CLK_20") (pintype "no_connect"))
    )
    (net (code "200") (name "unconnected-(X1-CMD-Pad18)") (class "Default")
      (node (ref "X1") (pin "18") (pinfunction "CMD_18") (pintype "no_connect"))
    )
    (net (code "201") (name "unconnected-(X1-EN-Pad2)") (class "Default")
      (node (ref "X1") (pin "2") (pinfunction "EN_2") (pintype "bidirectional"))
    )
    (net (code "202") (name "unconnected-(X1-GPIO0{slash}ADC2_CH1{slash}BOOT-Pad25)") (class "Default")
      (node (ref "X1") (pin "25") (pinfunction "GPIO0/ADC2_CH1/BOOT_25") (pintype "bidirectional"))
    )
    (net (code "203") (name "unconnected-(X1-GPIO1{slash}TX-Pad35)") (class "Default")
      (node (ref "X1") (pin "35") (pinfunction "GPIO1/TX_35") (pintype "bidirectional"))
    )
    (net (code "204") (name "unconnected-(X1-GPIO2{slash}ADC2_CH2-Pad24)") (class "Default")
      (node (ref "X1") (pin "24") (pinfunction "GPIO2/ADC2_CH2_24") (pintype "bidirectional"))
    )
    (net (code "205") (name "unconnected-(X1-GPIO3{slash}RX-Pad34)") (class "Default")
      (node (ref "X1") (pin "34") (pinfunction "GPIO3/RX_34") (pintype "bidirectional"))
    )
    (net (code "206") (name "unconnected-(X1-GPIO15{slash}ADC2_CH3{slash}HCS-Pad23)") (class "Default")
      (node (ref "X1") (pin "23") (pinfunction "GPIO15/ADC2_CH3/HCS_23") (pintype "bidirectional"))
    )
    (net (code "207") (name "unconnected-(X1-SD0-Pad21)") (class "Default")
      (node (ref "X1") (pin "21") (pinfunction "SD0_21") (pintype "no_connect"))
    )
    (net (code "208") (name "unconnected-(X1-SD1-Pad22)") (class "Default")
      (node (ref "X1") (pin "22") (pinfunction "SD1_22") (pintype "no_connect"))
    )
    (net (code "209") (name "unconnected-(X1-SD2-Pad16)") (class "Default")
      (node (ref "X1") (pin "16") (pinfunction "SD2_16") (pintype "no_connect"))
    )
    (net (code "210") (name "unconnected-(X1-SD3-Pad17)") (class "Default")
      (node (ref "X1") (pin "17") (pinfunction "SD3_17") (pintype "no_connect"))
    )
    (net (code "211") (name "unconnected-(X1-SN-Pad4)") (class "Default")
      (node (ref "X1") (pin "4") (pinfunction "SN_4") (pintype "input"))
    )
    (net (code "212") (name "unconnected-(X1-SP-Pad3)") (class "Default")
      (node (ref "X1") (pin "3") (pinfunction "SP_3") (pintype "input"))
    )
    (net (code "213") (name "unconnected-(X2-Pad1)") (class "Default")
      (node (ref "X2") (pin "1") (pinfunction "1_1") (pintype "passive"))
    )
    (net (code "214") (name "~{CS}_A") (class "Default")
      (node (ref "D1") (pin "1") (pinfunction "A_1") (pintype "bidirectional"))
      (node (ref "X1") (pin "29") (pinfunction "GPIO5/VCS_29") (pintype "bidirectional"))
    )
    (net (code "215") (name "~{CS}_B") (class "Default")
      (node (ref "D1") (pin "2") (pinfunction "B_2") (pintype "bidirectional"))
      (node (ref "X1") (pin "33") (pinfunction "GPIO21_33") (pintype "bidirectional"))
    )
    (net (code "216") (name "~{CS}_C") (class "Default")
      (node (ref "D1") (pin "3") (pinfunction "C_3") (pintype "bidirectional"))
      (node (ref "X1") (pin "36") (pinfunction "GPIO22_36") (pintype "bidirectional"))
    )
  )
)
